# Math.net
KiCad netlist of a schematic drawn in EAGLE
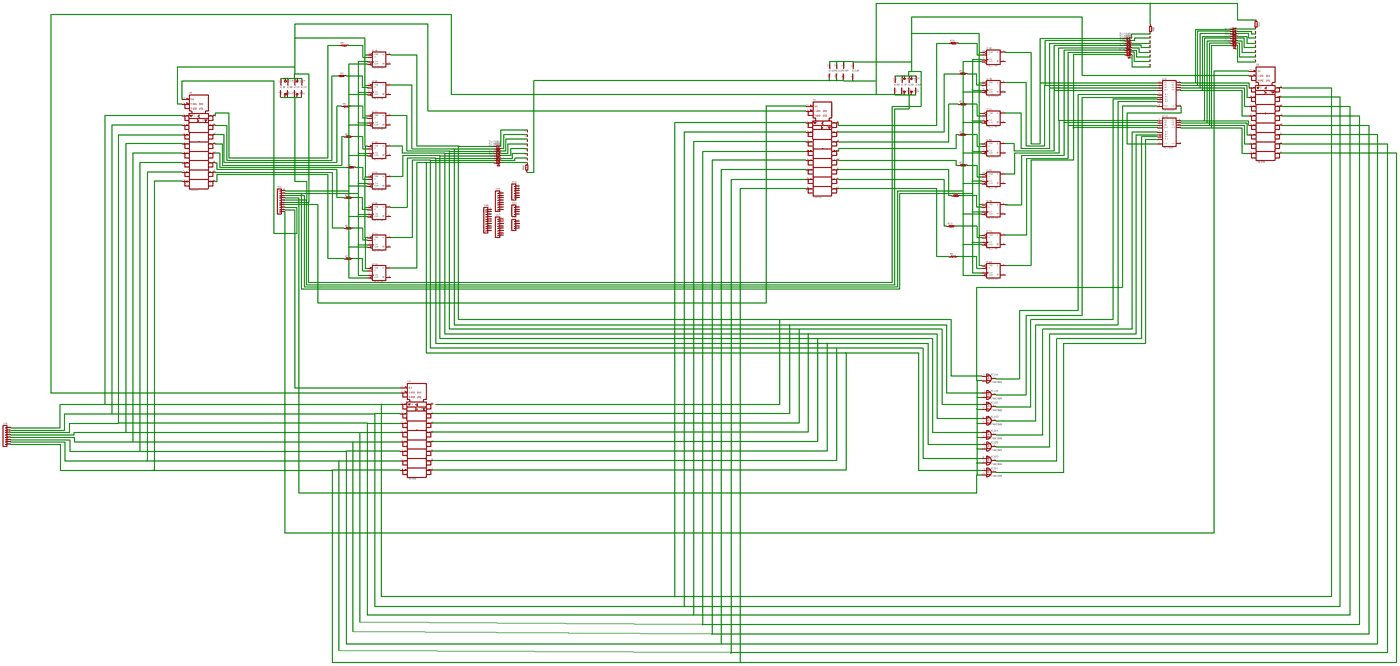
[diagram p0: schematic, sheet 1, overview]
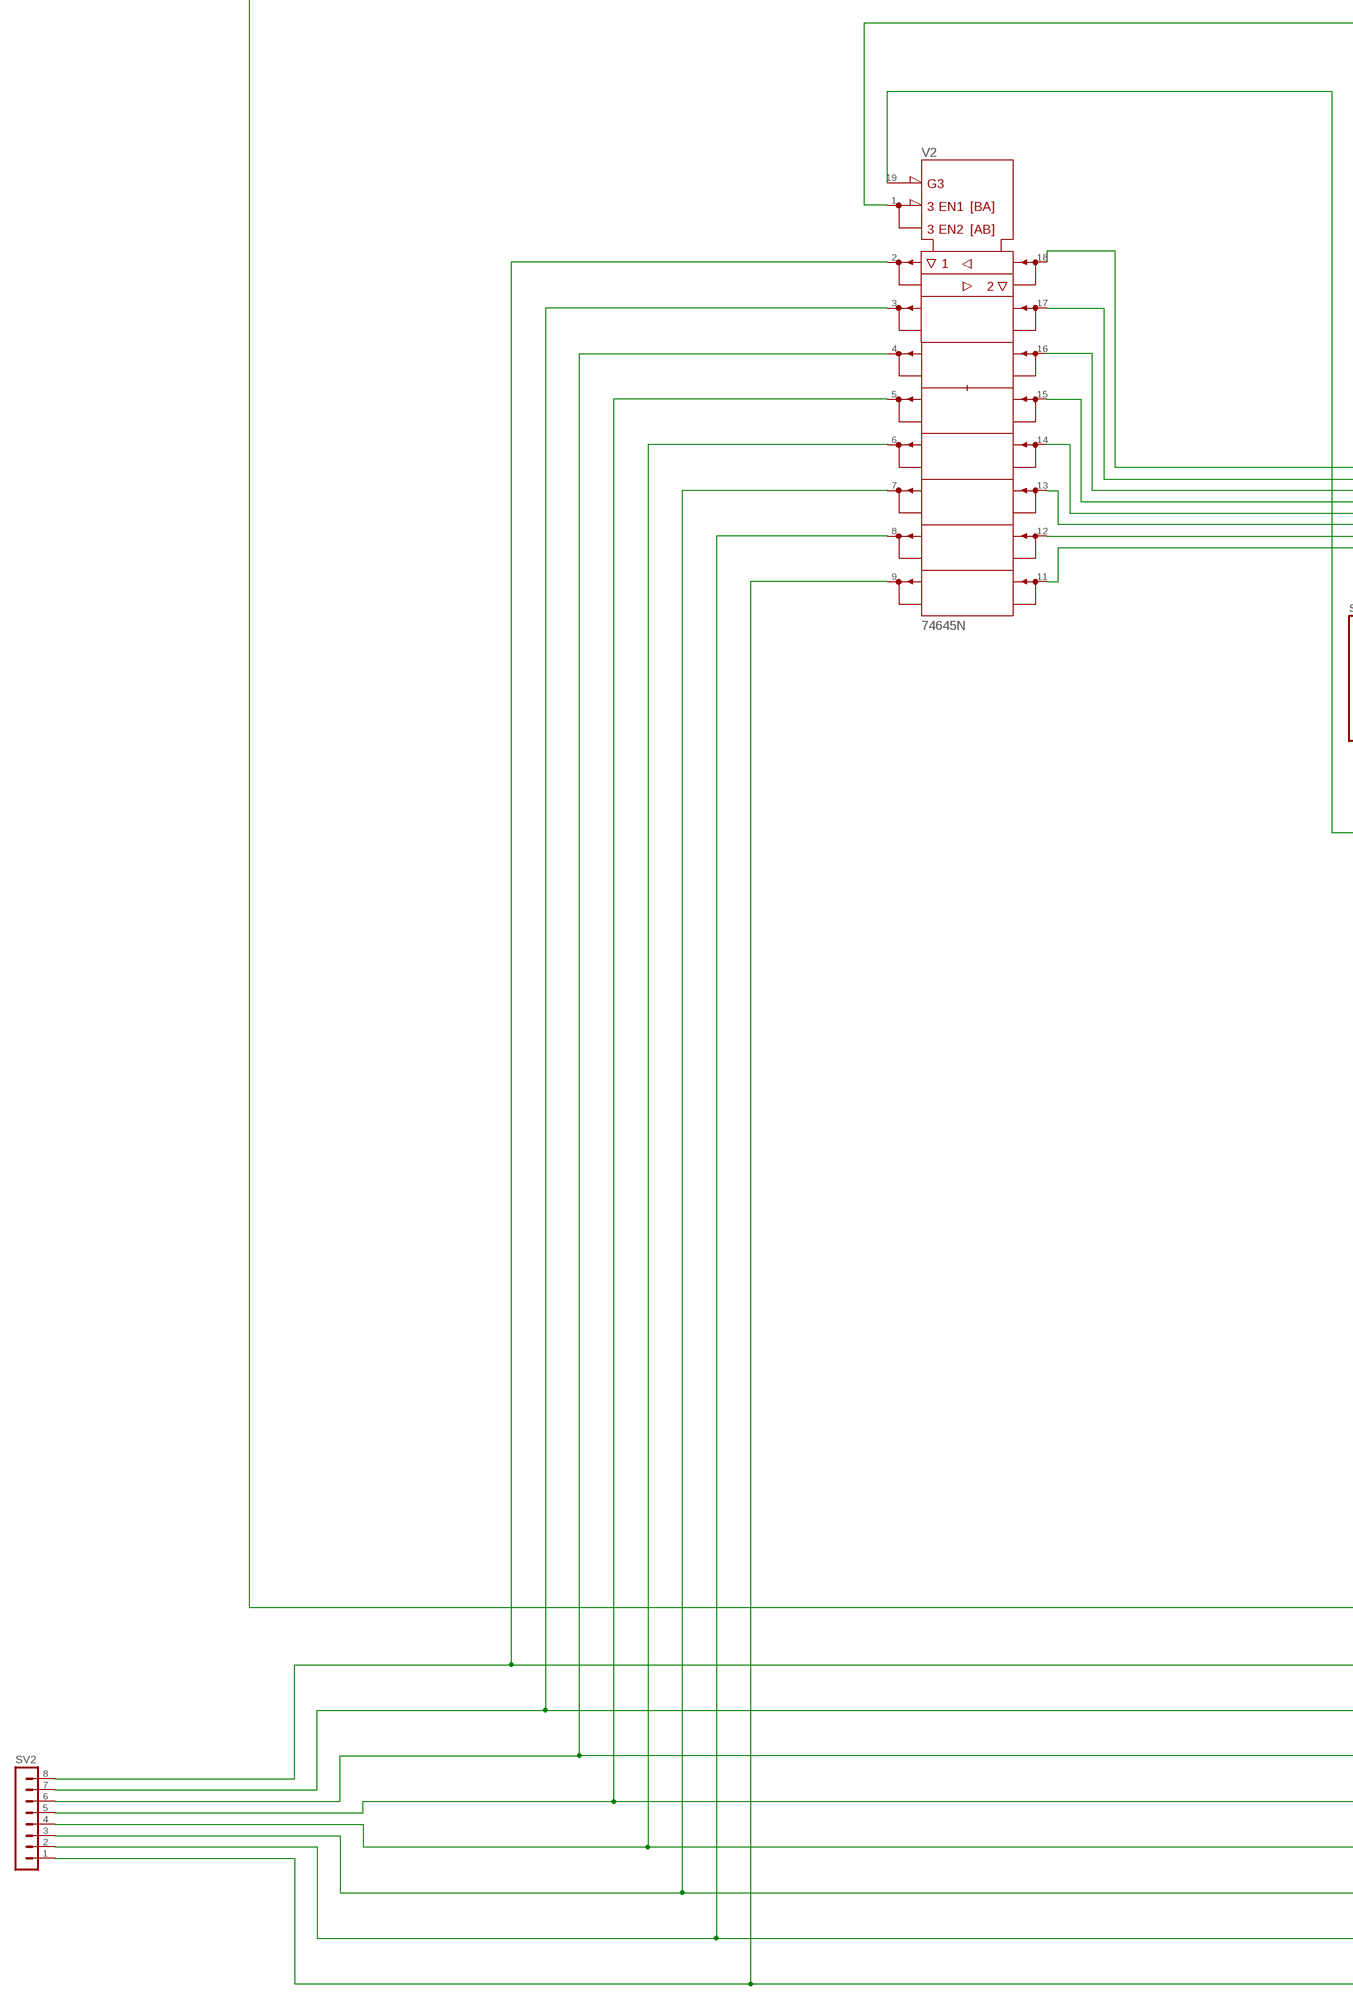
[diagram p1: schematic, sheet 1, part 1 of 6]
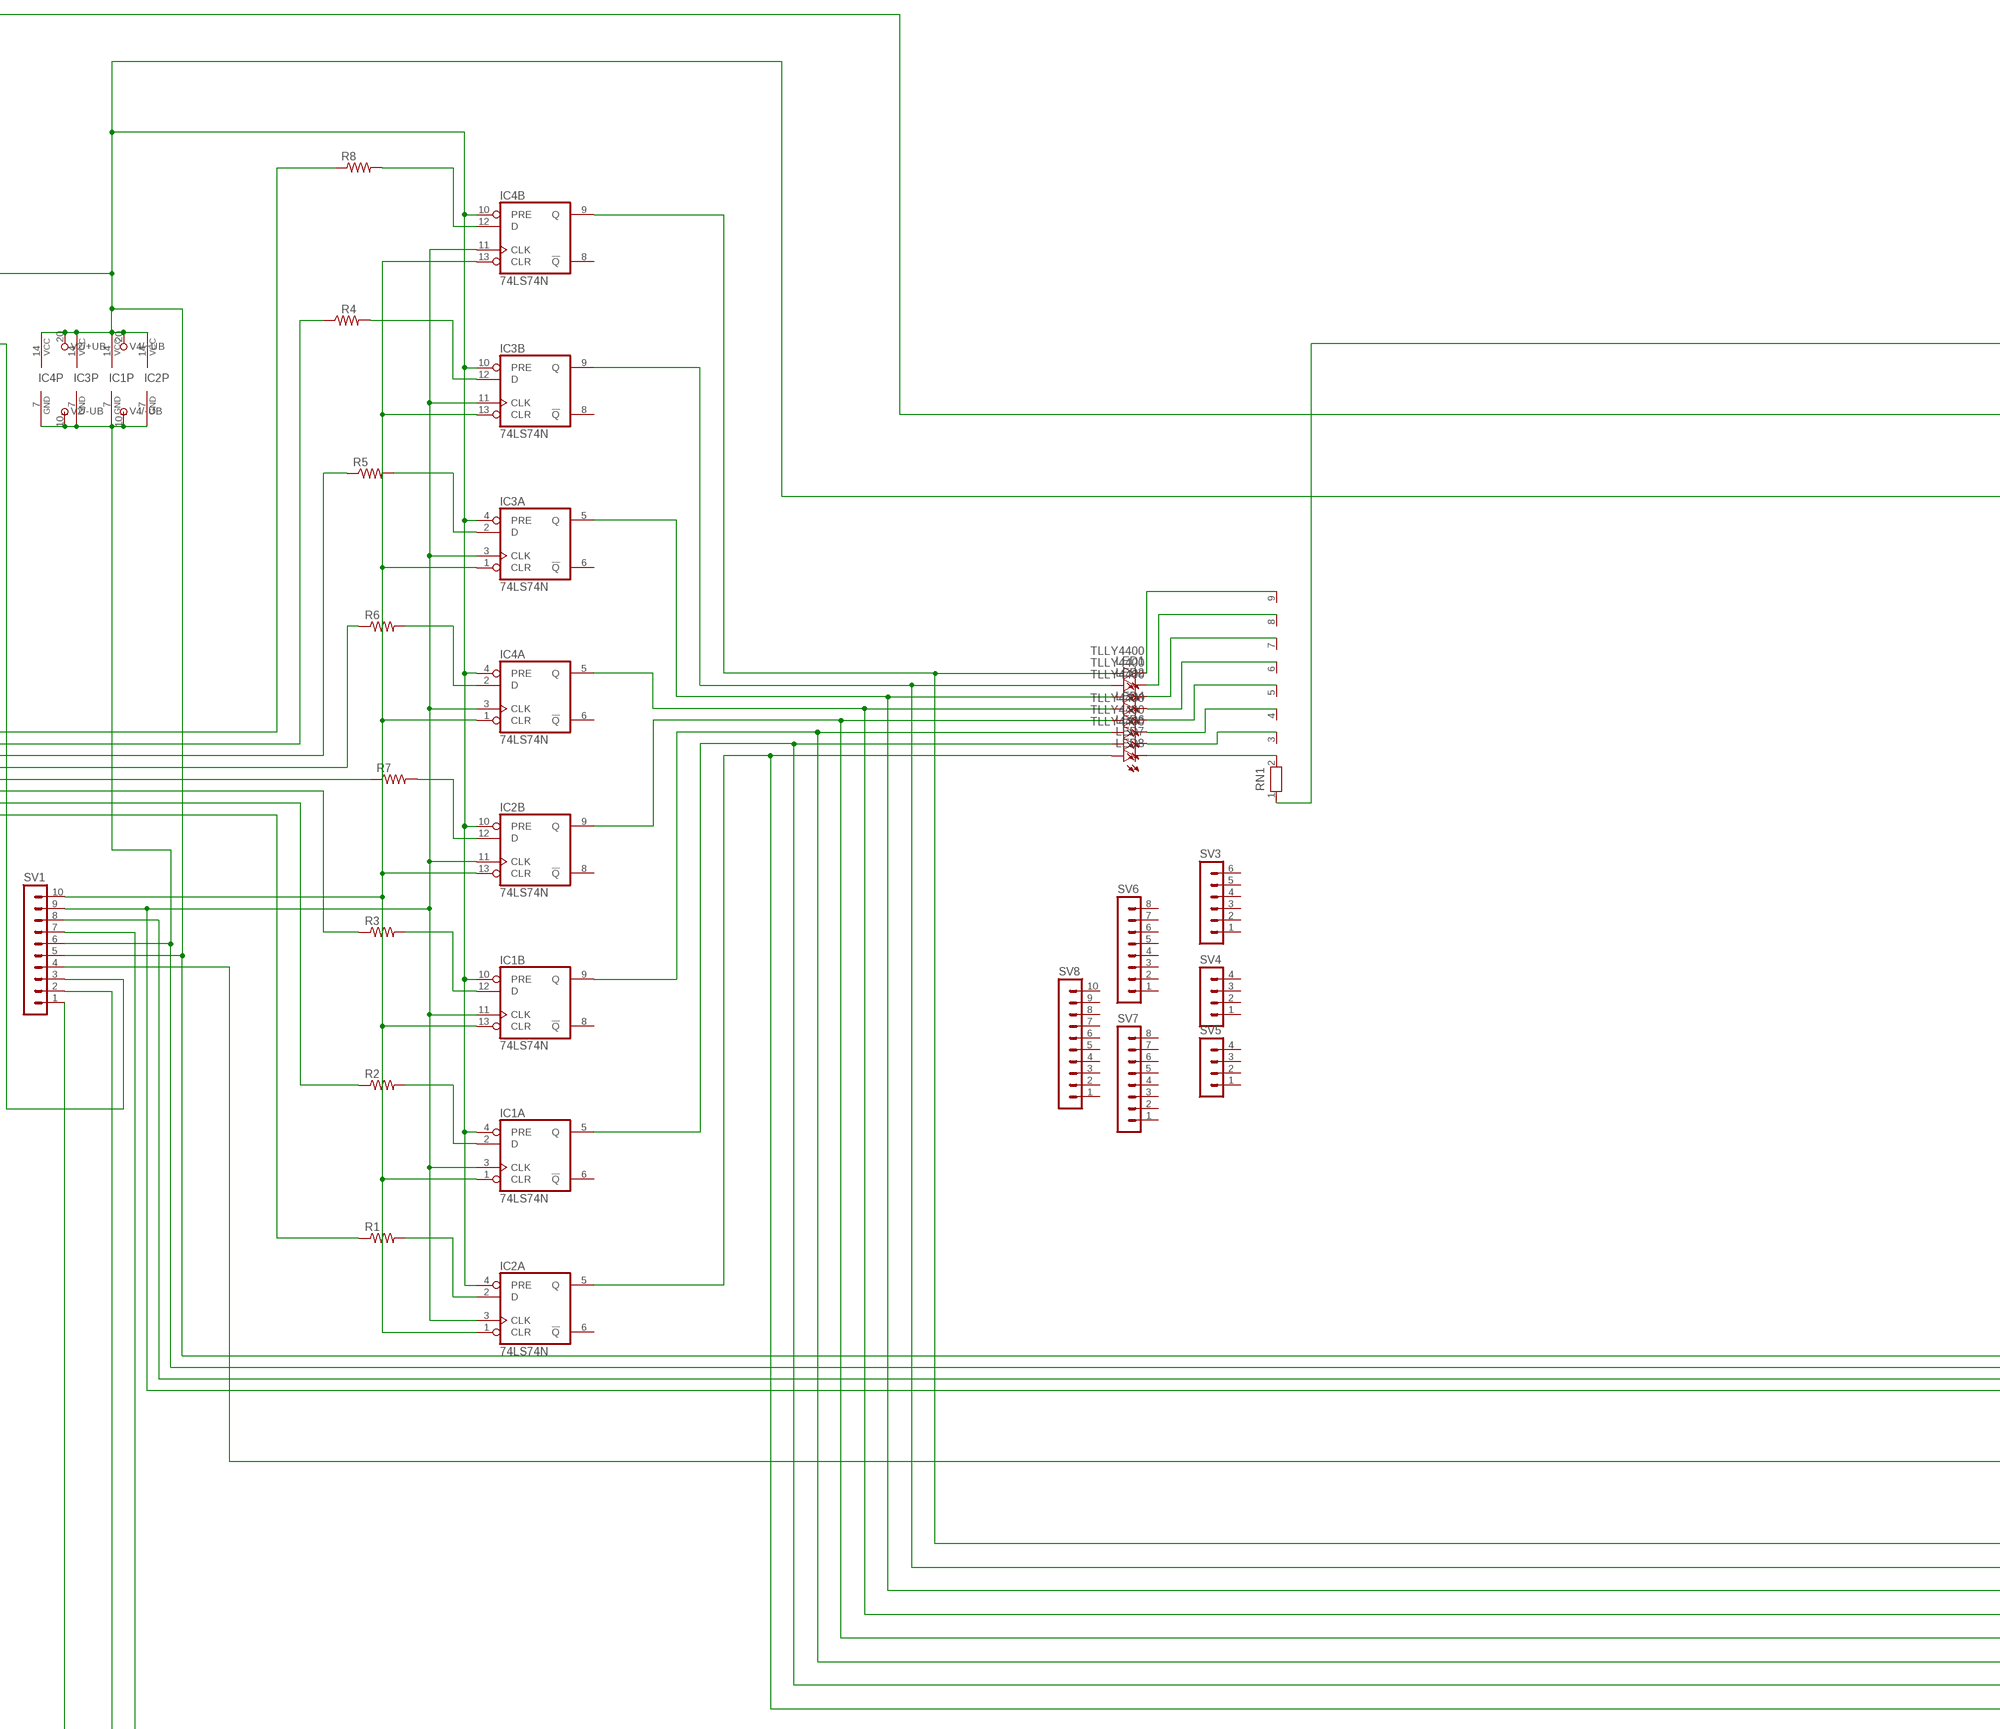
[diagram p2: schematic, sheet 1, part 2 of 6]
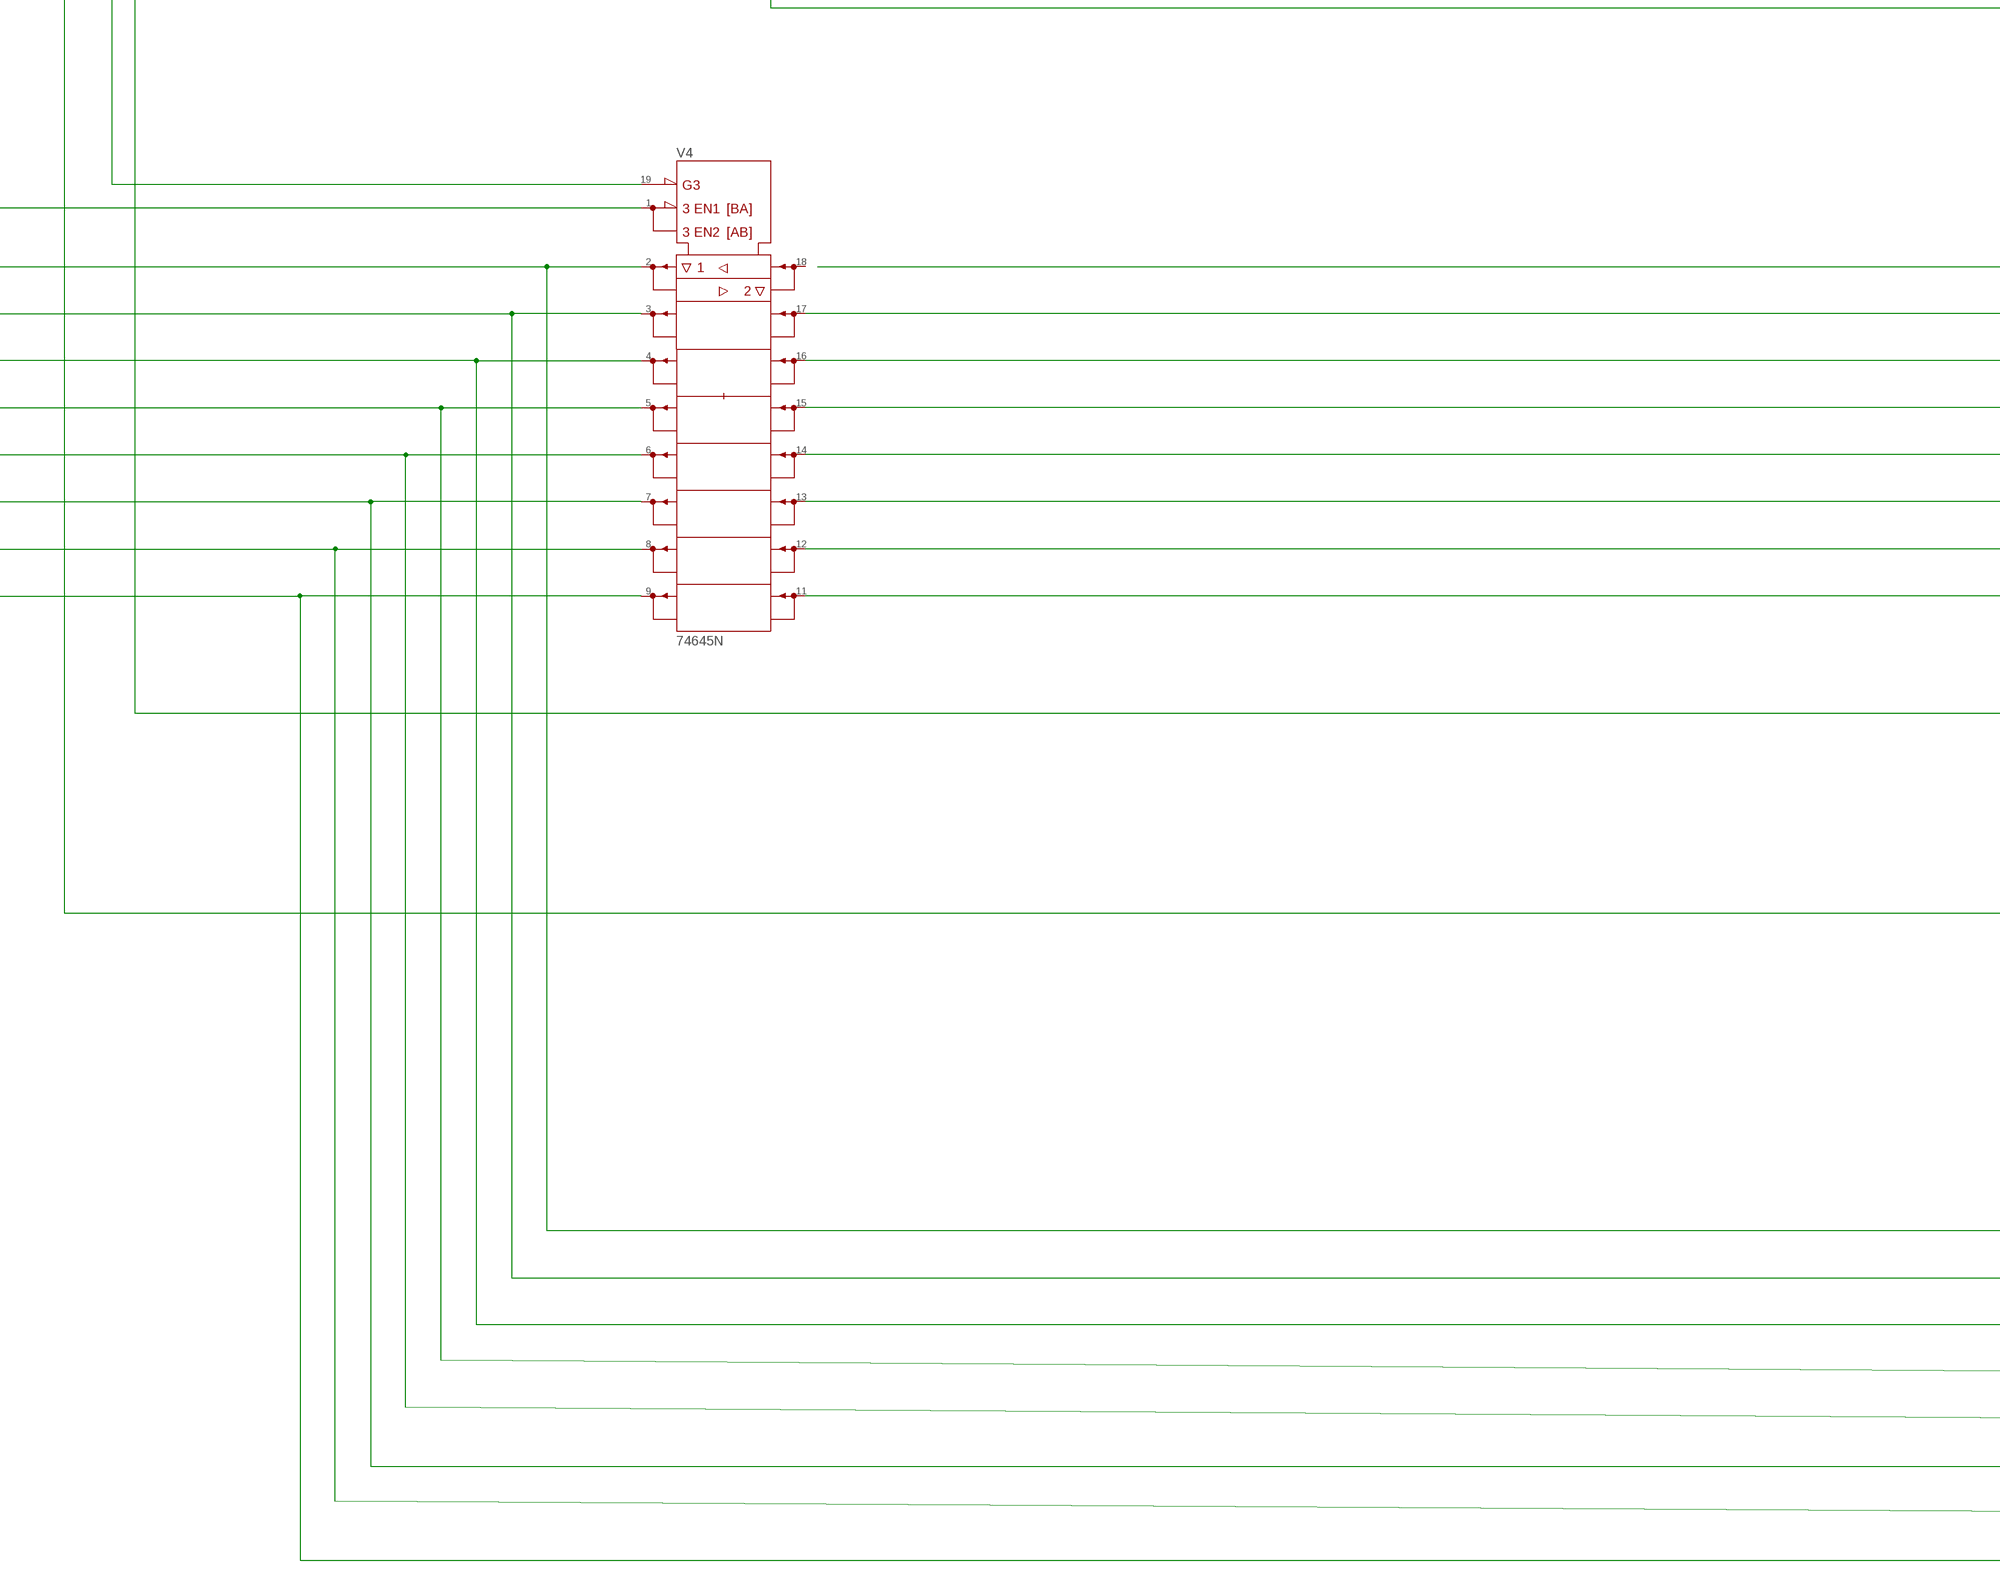
[diagram p3: schematic, sheet 1, part 3 of 6]
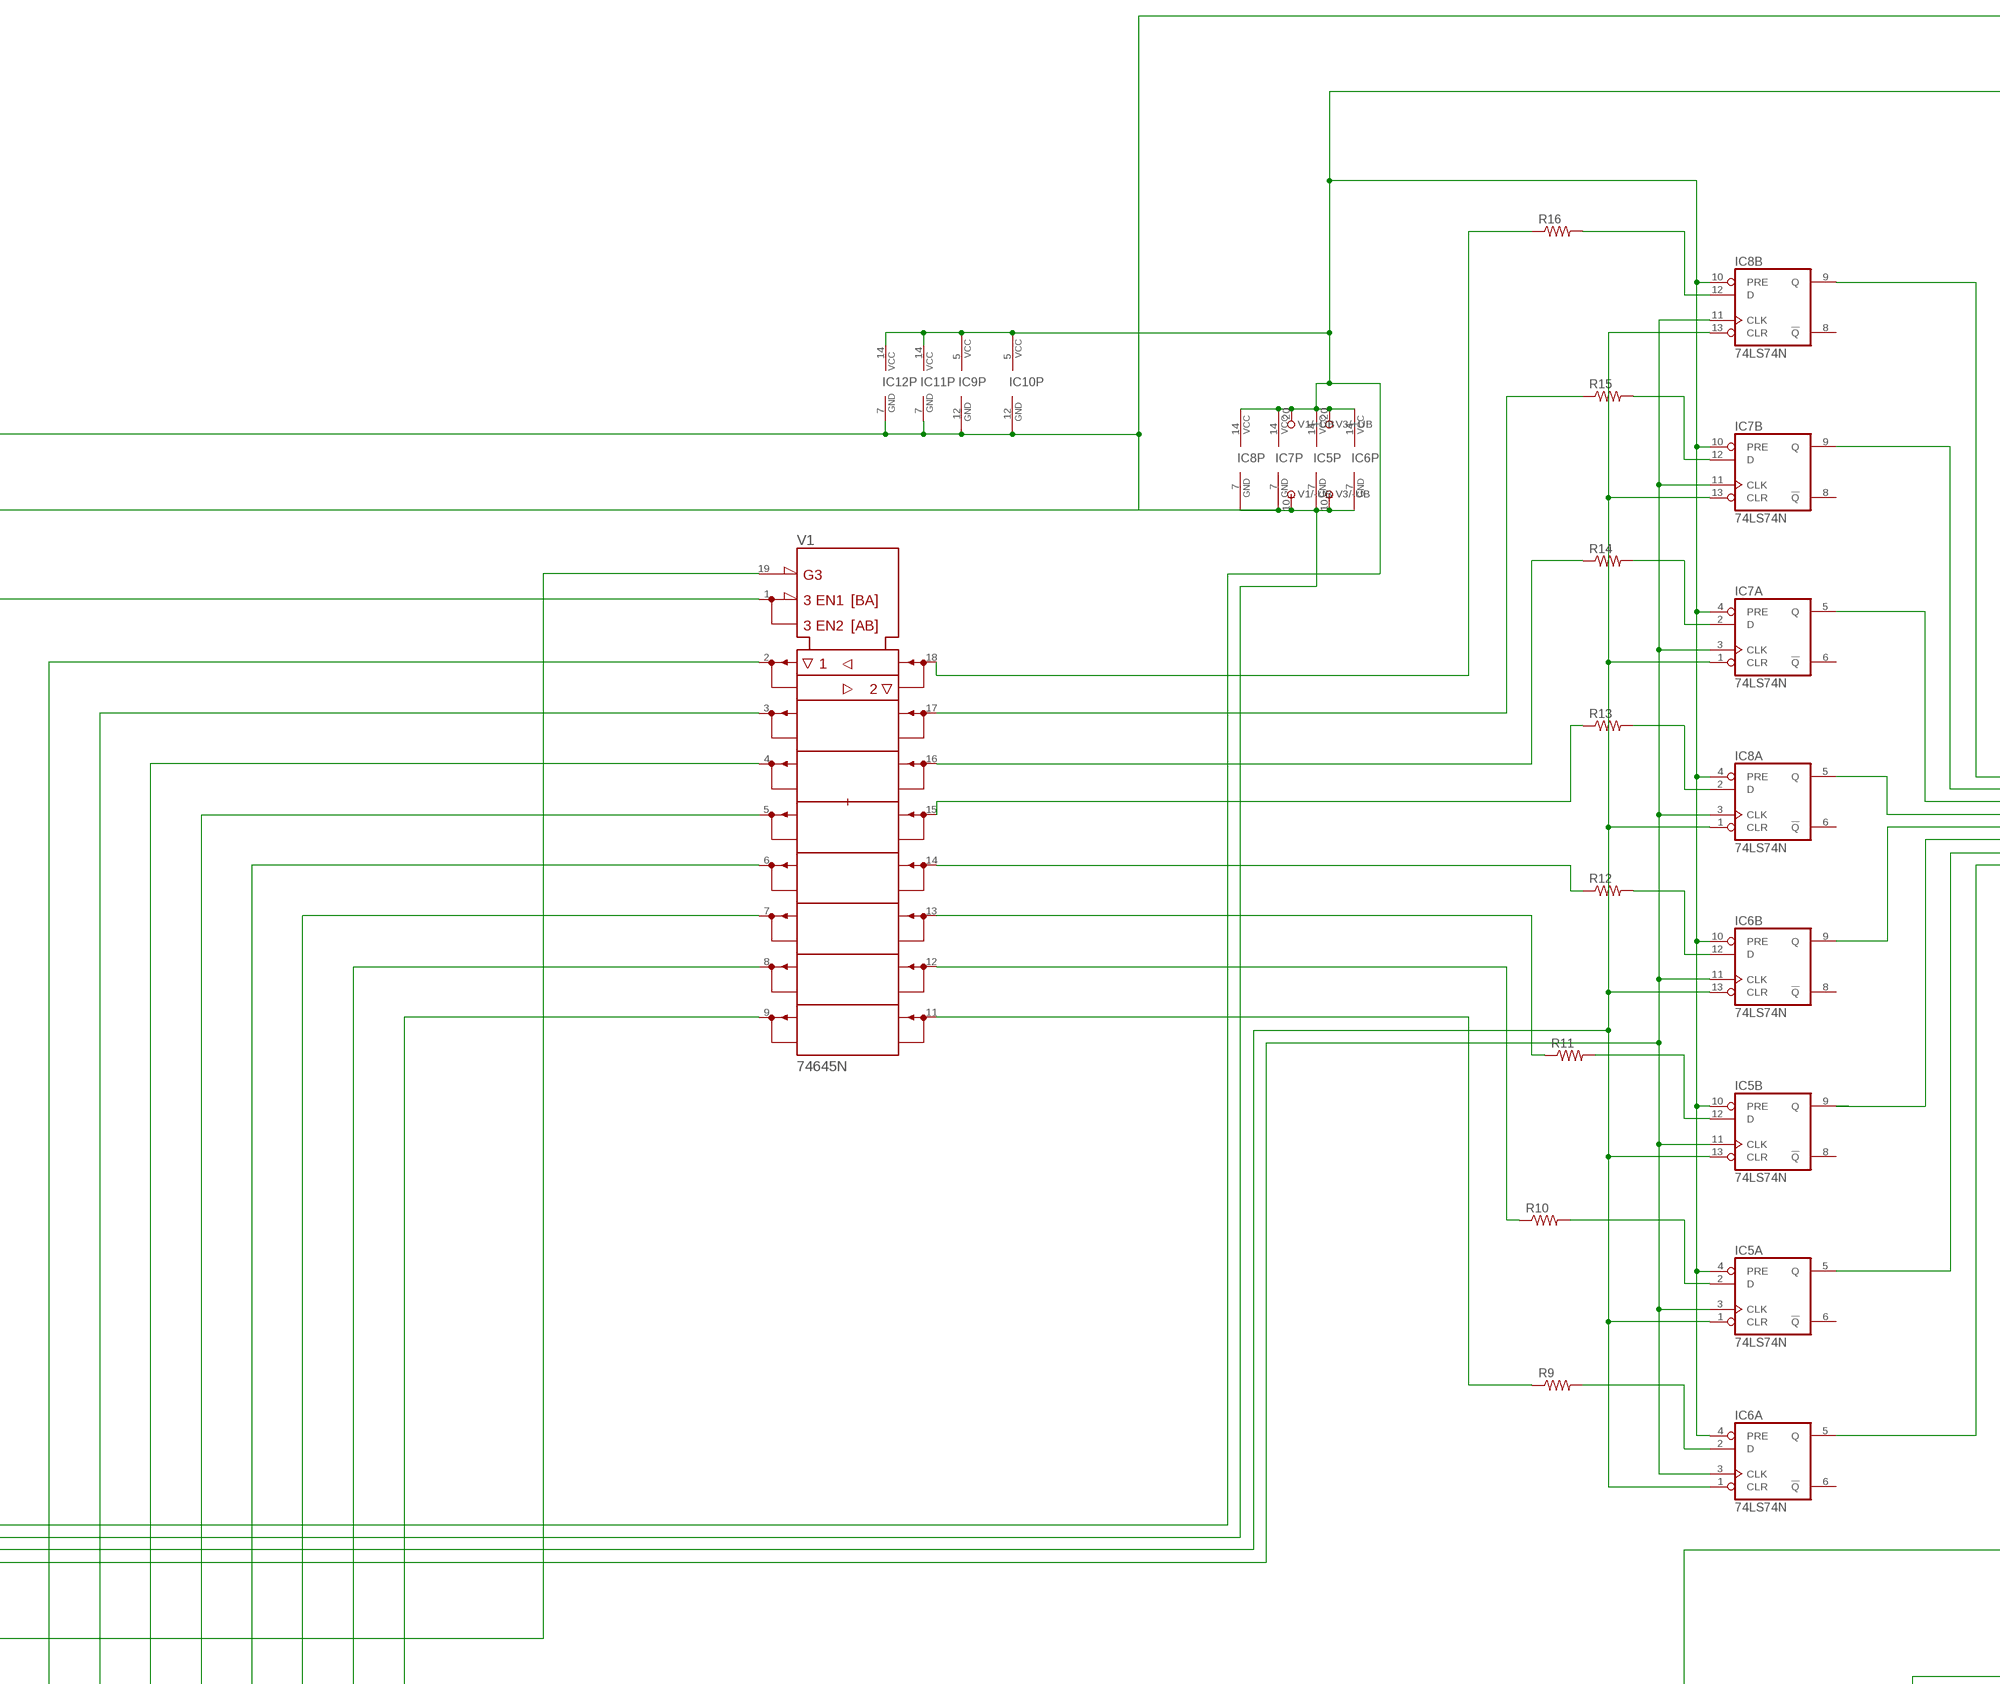
[diagram p4: schematic, sheet 1, part 4 of 6]
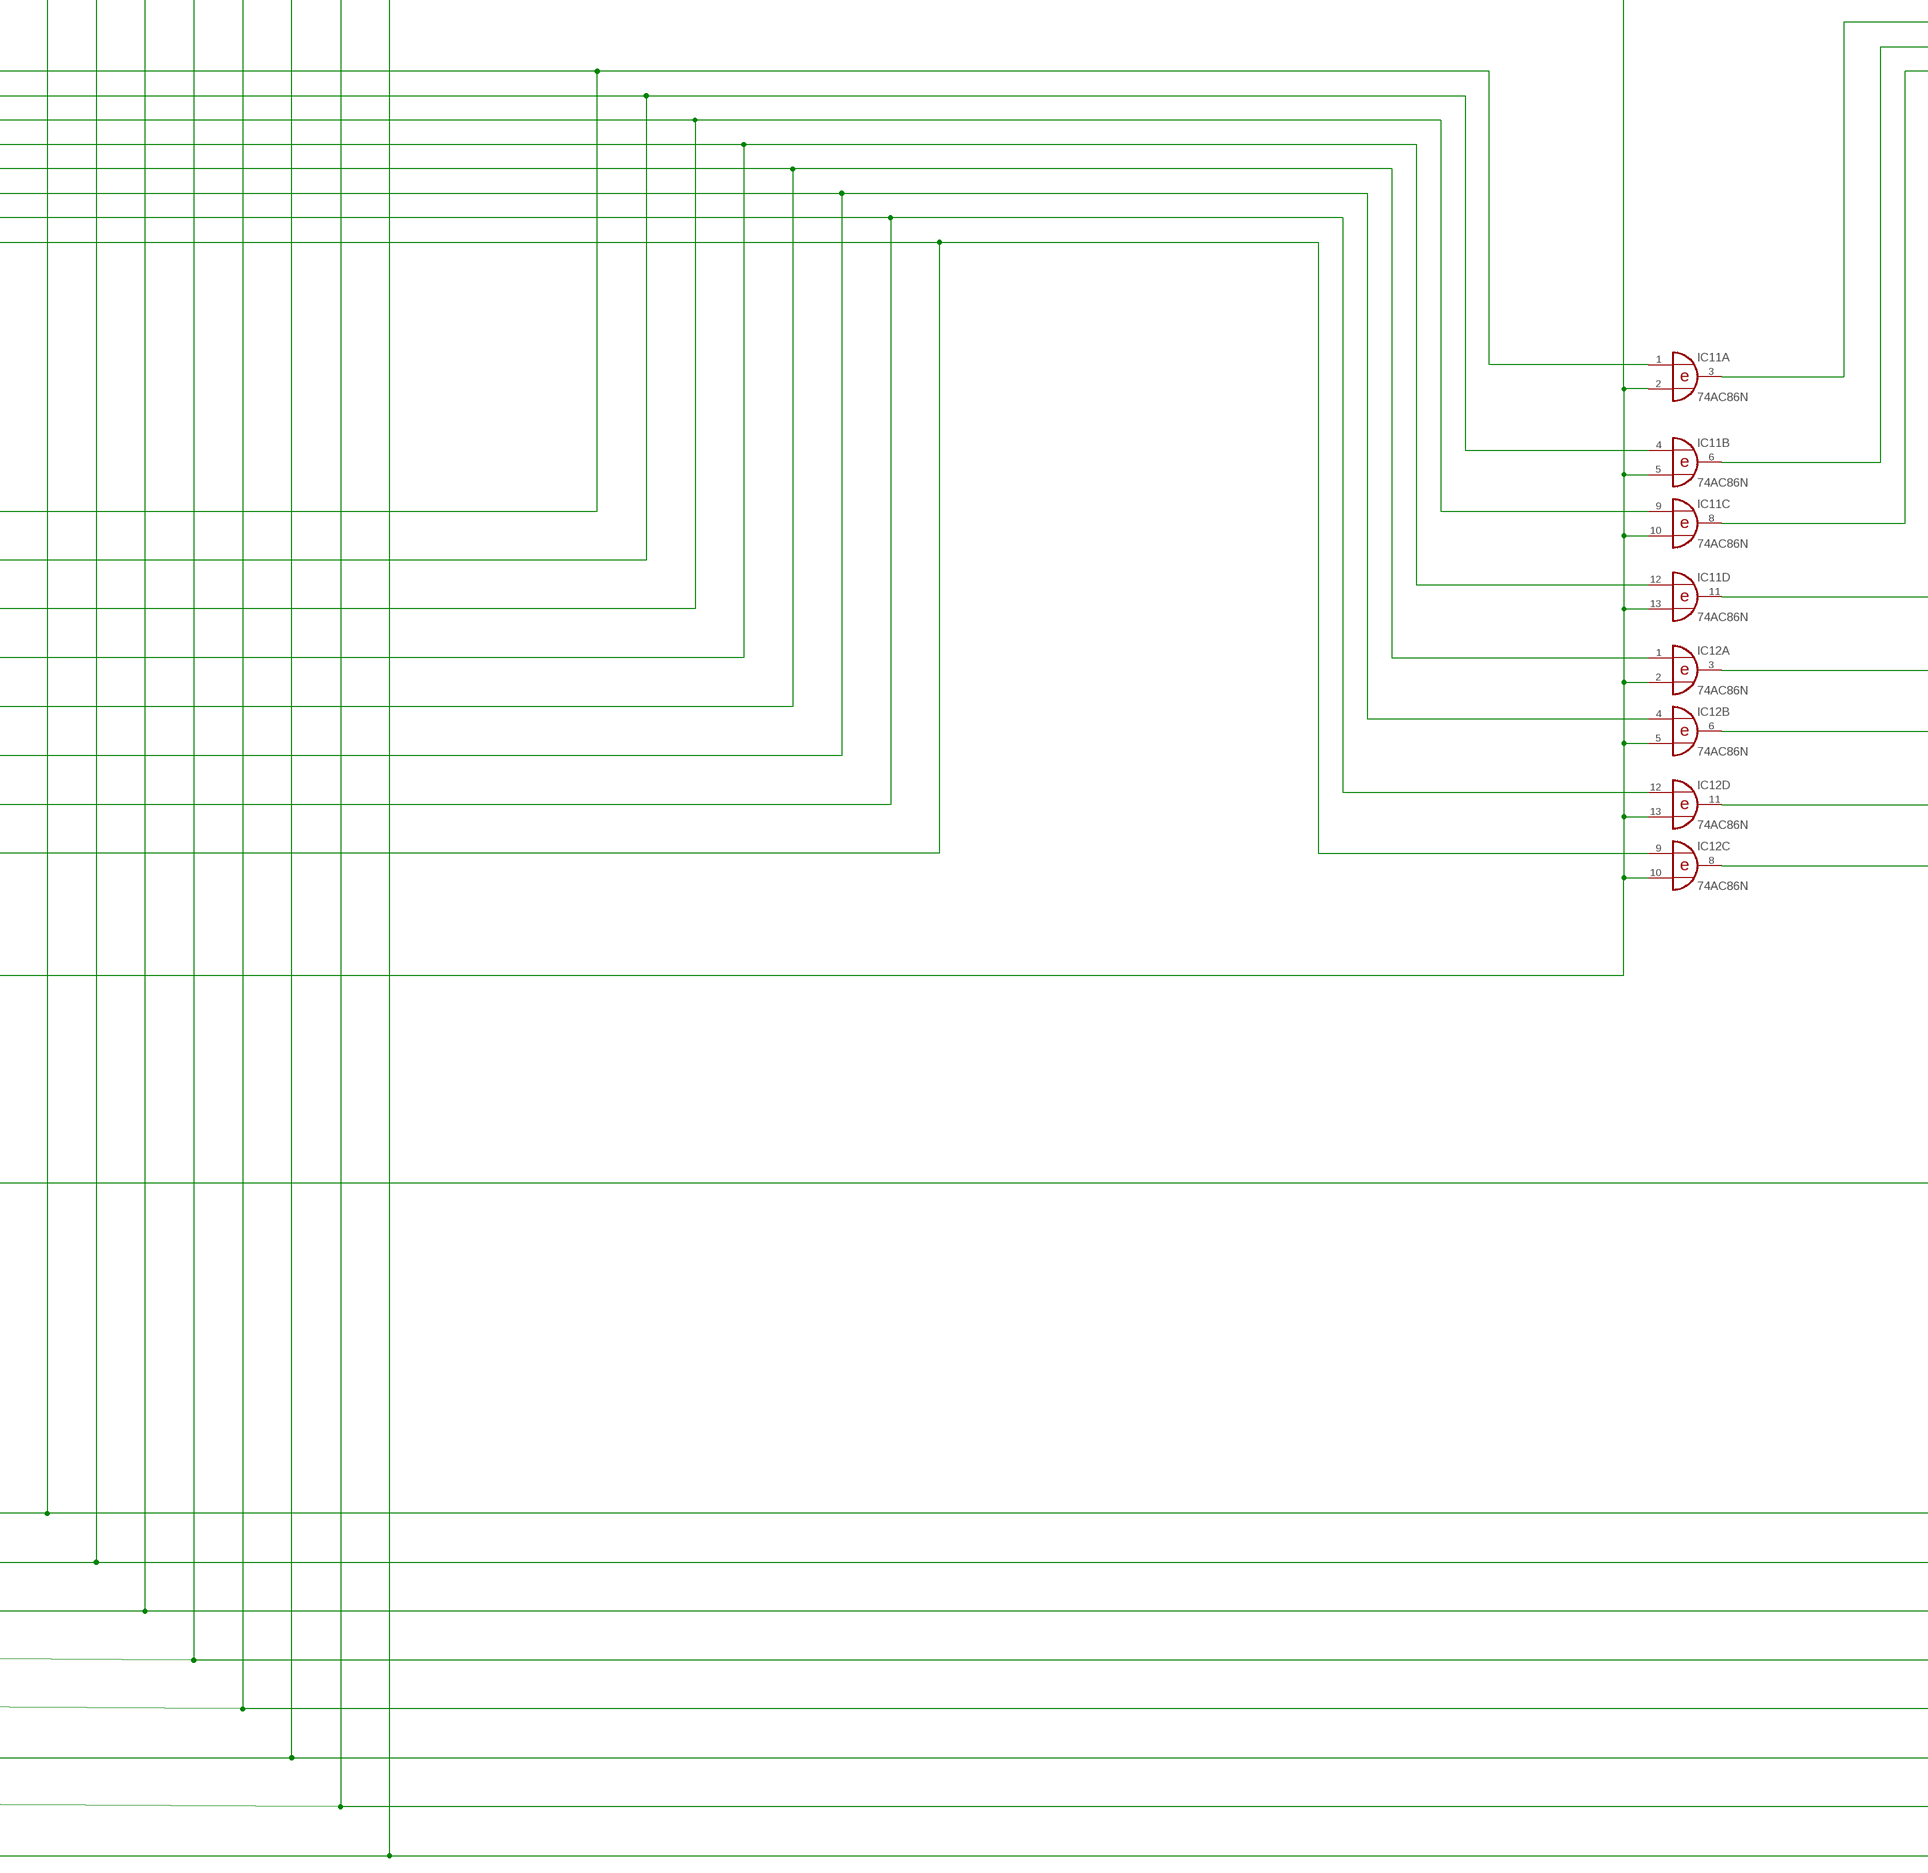
[diagram p5: schematic, sheet 1, part 5 of 6]
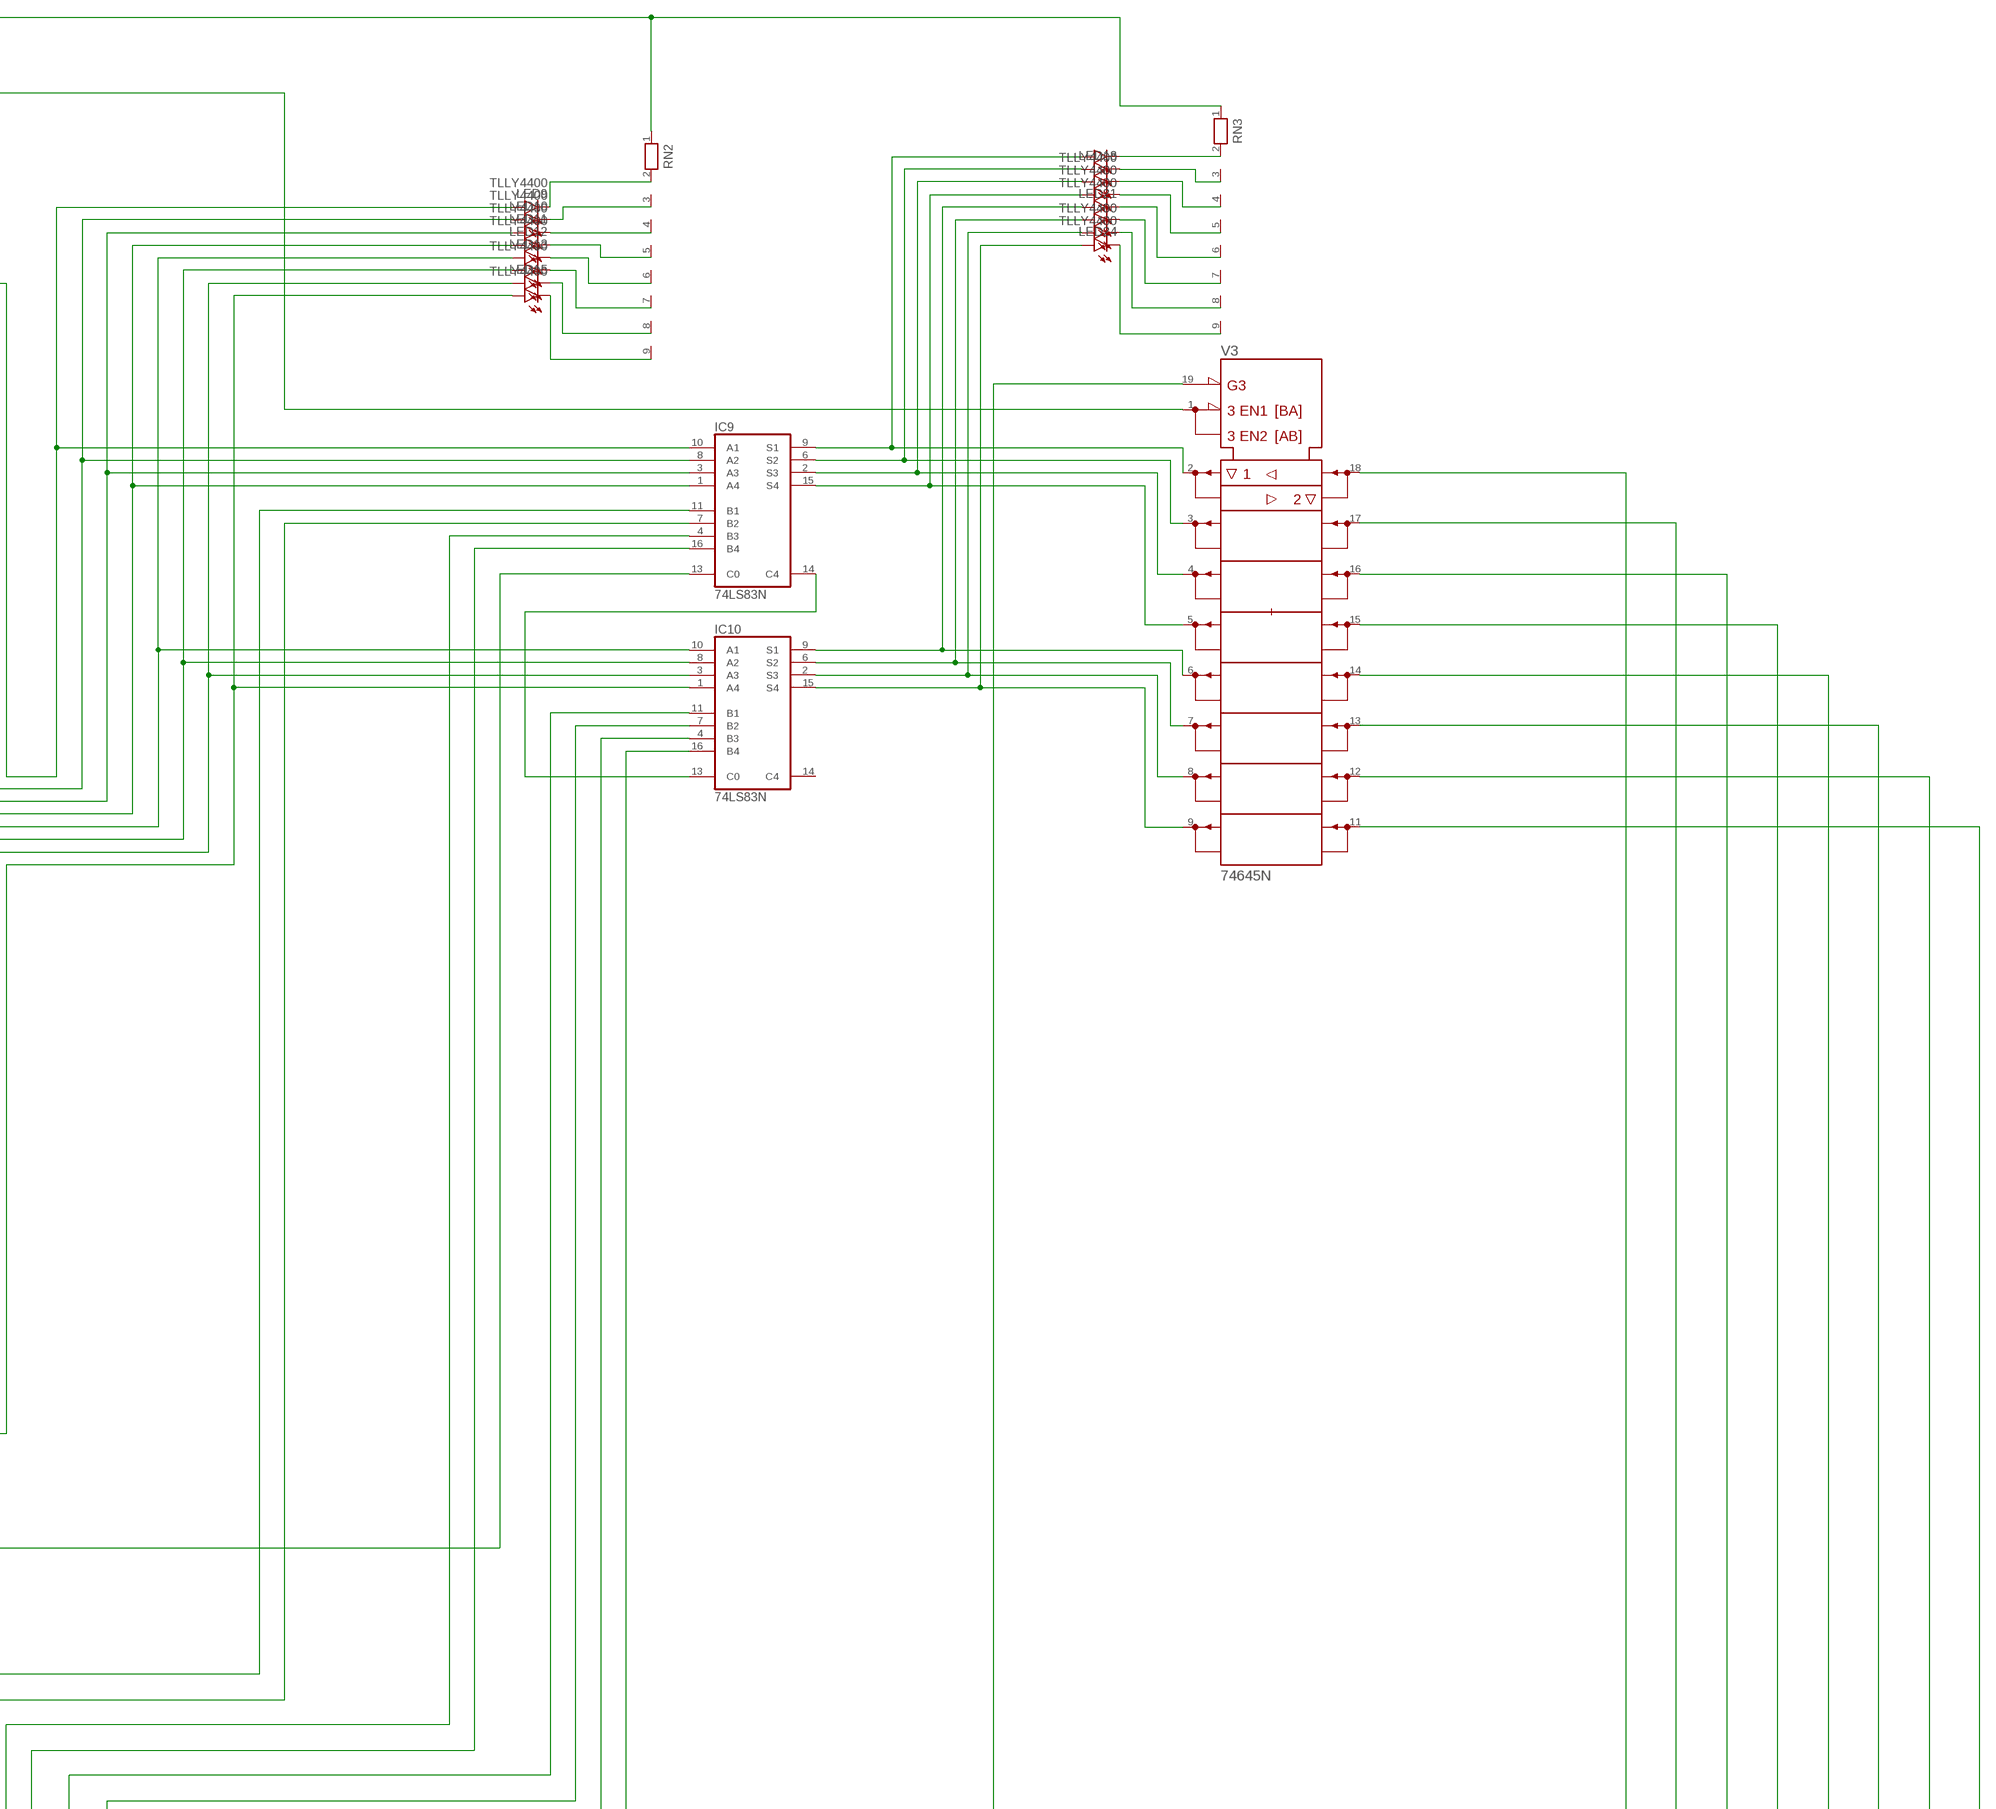
[diagram p6: schematic, sheet 1, part 6 of 6]

(export (version "E")
  (design (tool "Eeschema 10.0.6"))
  (components
    (comp (ref "IC1")
      (value "74LS74N")
      (footprint "eagle-import:DIL14")
      (libsource (lib "eagle-import") (part "7474NLS"))
    )
    (comp (ref "IC2")
      (value "74LS74N")
      (footprint "eagle-import:DIL14")
      (libsource (lib "eagle-import") (part "7474NLS"))
    )
    (comp (ref "IC3")
      (value "74LS74N")
      (footprint "eagle-import:DIL14")
      (libsource (lib "eagle-import") (part "7474NLS"))
    )
    (comp (ref "IC4")
      (value "74LS74N")
      (footprint "eagle-import:DIL14")
      (libsource (lib "eagle-import") (part "7474NLS"))
    )
    (comp (ref "IC5")
      (value "74LS74N")
      (footprint "eagle-import:DIL14")
      (libsource (lib "eagle-import") (part "7474NLS"))
    )
    (comp (ref "IC6")
      (value "74LS74N")
      (footprint "eagle-import:DIL14")
      (libsource (lib "eagle-import") (part "7474NLS"))
    )
    (comp (ref "IC7")
      (value "74LS74N")
      (footprint "eagle-import:DIL14")
      (libsource (lib "eagle-import") (part "7474NLS"))
    )
    (comp (ref "IC8")
      (value "74LS74N")
      (footprint "eagle-import:DIL14")
      (libsource (lib "eagle-import") (part "7474NLS"))
    )
    (comp (ref "IC9")
      (value "74LS83N")
      (footprint "eagle-import:DIL16")
      (libsource (lib "eagle-import") (part "7483NLS"))
    )
    (comp (ref "IC10")
      (value "74LS83N")
      (footprint "eagle-import:DIL16")
      (libsource (lib "eagle-import") (part "7483NLS"))
    )
    (comp (ref "IC11")
      (value "74AC86N")
      (footprint "eagle-import:DIL14")
      (libsource (lib "eagle-import") (part "7486NAC"))
    )
    (comp (ref "IC12")
      (value "74AC86N")
      (footprint "eagle-import:DIL14")
      (libsource (lib "eagle-import") (part "7486NAC"))
    )
    (comp (ref "LED1")
      (value "TLLY4400")
      (footprint "eagle-import:LED3MM")
      (fields (field (name "MF") "VISHAY SEMICONDUCTOR"))
      (libsource (lib "eagle-import") (part "TLLY4400"))
    )
    (comp (ref "LED2")
      (value "TLLY4400")
      (footprint "eagle-import:LED3MM")
      (fields (field (name "MF") "VISHAY SEMICONDUCTOR"))
      (libsource (lib "eagle-import") (part "TLLY4400"))
    )
    (comp (ref "LED3")
      (value "TLLY4400")
      (footprint "eagle-import:LED3MM")
      (fields (field (name "MF") "VISHAY SEMICONDUCTOR"))
      (libsource (lib "eagle-import") (part "TLLY4400"))
    )
    (comp (ref "LED4")
      (value "TLLY4400")
      (footprint "eagle-import:LED3MM")
      (fields (field (name "MF") "VISHAY SEMICONDUCTOR"))
      (libsource (lib "eagle-import") (part "TLLY4400"))
    )
    (comp (ref "LED5")
      (value "TLLY4400")
      (footprint "eagle-import:LED3MM")
      (fields (field (name "MF") "VISHAY SEMICONDUCTOR"))
      (libsource (lib "eagle-import") (part "TLLY4400"))
    )
    (comp (ref "LED6")
      (value "TLLY4400")
      (footprint "eagle-import:LED3MM")
      (fields (field (name "MF") "VISHAY SEMICONDUCTOR"))
      (libsource (lib "eagle-import") (part "TLLY4400"))
    )
    (comp (ref "LED7")
      (value "TLLY4400")
      (footprint "eagle-import:LED3MM")
      (fields (field (name "MF") "VISHAY SEMICONDUCTOR"))
      (libsource (lib "eagle-import") (part "TLLY4400"))
    )
    (comp (ref "LED8")
      (value "TLLY4400")
      (footprint "eagle-import:LED3MM")
      (fields (field (name "MF") "VISHAY SEMICONDUCTOR"))
      (libsource (lib "eagle-import") (part "TLLY4400"))
    )
    (comp (ref "LED9")
      (value "TLLY4400")
      (footprint "eagle-import:LED3MM")
      (fields (field (name "MF") "VISHAY SEMICONDUCTOR"))
      (libsource (lib "eagle-import") (part "TLLY4400"))
    )
    (comp (ref "LED10")
      (value "TLLY4400")
      (footprint "eagle-import:LED3MM")
      (fields (field (name "MF") "VISHAY SEMICONDUCTOR"))
      (libsource (lib "eagle-import") (part "TLLY4400"))
    )
    (comp (ref "LED11")
      (value "TLLY4400")
      (footprint "eagle-import:LED3MM")
      (fields (field (name "MF") "VISHAY SEMICONDUCTOR"))
      (libsource (lib "eagle-import") (part "TLLY4400"))
    )
    (comp (ref "LED12")
      (value "TLLY4400")
      (footprint "eagle-import:LED3MM")
      (fields (field (name "MF") "VISHAY SEMICONDUCTOR"))
      (libsource (lib "eagle-import") (part "TLLY4400"))
    )
    (comp (ref "LED13")
      (value "TLLY4400")
      (footprint "eagle-import:LED3MM")
      (fields (field (name "MF") "VISHAY SEMICONDUCTOR"))
      (libsource (lib "eagle-import") (part "TLLY4400"))
    )
    (comp (ref "LED14")
      (value "TLLY4400")
      (footprint "eagle-import:LED3MM")
      (fields (field (name "MF") "VISHAY SEMICONDUCTOR"))
      (libsource (lib "eagle-import") (part "TLLY4400"))
    )
    (comp (ref "LED15")
      (value "TLLY4400")
      (footprint "eagle-import:LED3MM")
      (fields (field (name "MF") "VISHAY SEMICONDUCTOR"))
      (libsource (lib "eagle-import") (part "TLLY4400"))
    )
    (comp (ref "LED16")
      (value "TLLY4400")
      (footprint "eagle-import:LED3MM")
      (fields (field (name "MF") "VISHAY SEMICONDUCTOR"))
      (libsource (lib "eagle-import") (part "TLLY4400"))
    )
    (comp (ref "LED17")
      (value "TLLY4400")
      (footprint "eagle-import:LED3MM")
      (fields (field (name "MF") "VISHAY SEMICONDUCTOR"))
      (libsource (lib "eagle-import") (part "TLLY4400"))
    )
    (comp (ref "LED18")
      (value "TLLY4400")
      (footprint "eagle-import:LED3MM")
      (fields (field (name "MF") "VISHAY SEMICONDUCTOR"))
      (libsource (lib "eagle-import") (part "TLLY4400"))
    )
    (comp (ref "LED19")
      (value "TLLY4400")
      (footprint "eagle-import:LED3MM")
      (fields (field (name "MF") "VISHAY SEMICONDUCTOR"))
      (libsource (lib "eagle-import") (part "TLLY4400"))
    )
    (comp (ref "LED20")
      (value "TLLY4400")
      (footprint "eagle-import:LED3MM")
      (fields (field (name "MF") "VISHAY SEMICONDUCTOR"))
      (libsource (lib "eagle-import") (part "TLLY4400"))
    )
    (comp (ref "LED21")
      (value "TLLY4400")
      (footprint "eagle-import:LED3MM")
      (fields (field (name "MF") "VISHAY SEMICONDUCTOR"))
      (libsource (lib "eagle-import") (part "TLLY4400"))
    )
    (comp (ref "LED22")
      (value "TLLY4400")
      (footprint "eagle-import:LED3MM")
      (fields (field (name "MF") "VISHAY SEMICONDUCTOR"))
      (libsource (lib "eagle-import") (part "TLLY4400"))
    )
    (comp (ref "LED23")
      (value "TLLY4400")
      (footprint "eagle-import:LED3MM")
      (fields (field (name "MF") "VISHAY SEMICONDUCTOR"))
      (libsource (lib "eagle-import") (part "TLLY4400"))
    )
    (comp (ref "LED24")
      (value "TLLY4400")
      (footprint "eagle-import:LED3MM")
      (fields (field (name "MF") "VISHAY SEMICONDUCTOR"))
      (libsource (lib "eagle-import") (part "TLLY4400"))
    )
    (comp (ref "R1")
      (value "R-US_0207/2V")
      (footprint "eagle-import:0207_2V")
      (libsource (lib "eagle-import") (part "R-US_0207/2V"))
    )
    (comp (ref "R2")
      (value "R-US_0207/2V")
      (footprint "eagle-import:0207_2V")
      (libsource (lib "eagle-import") (part "R-US_0207/2V"))
    )
    (comp (ref "R3")
      (value "R-US_0207/2V")
      (footprint "eagle-import:0207_2V")
      (libsource (lib "eagle-import") (part "R-US_0207/2V"))
    )
    (comp (ref "R4")
      (value "R-US_0207/2V")
      (footprint "eagle-import:0207_2V")
      (libsource (lib "eagle-import") (part "R-US_0207/2V"))
    )
    (comp (ref "R5")
      (value "R-US_0207/2V")
      (footprint "eagle-import:0207_2V")
      (libsource (lib "eagle-import") (part "R-US_0207/2V"))
    )
    (comp (ref "R6")
      (value "R-US_0207/2V")
      (footprint "eagle-import:0207_2V")
      (libsource (lib "eagle-import") (part "R-US_0207/2V"))
    )
    (comp (ref "R7")
      (value "R-US_0207/2V")
      (footprint "eagle-import:0207_2V")
      (libsource (lib "eagle-import") (part "R-US_0207/2V"))
    )
    (comp (ref "R8")
      (value "R-US_0207/2V")
      (footprint "eagle-import:0207_2V")
      (libsource (lib "eagle-import") (part "R-US_0207/2V"))
    )
    (comp (ref "R9")
      (value "R-US_0207/2V")
      (footprint "eagle-import:0207_2V")
      (libsource (lib "eagle-import") (part "R-US_0207/2V"))
    )
    (comp (ref "R10")
      (value "R-US_0207/2V")
      (footprint "eagle-import:0207_2V")
      (libsource (lib "eagle-import") (part "R-US_0207/2V"))
    )
    (comp (ref "R11")
      (value "R-US_0207/2V")
      (footprint "eagle-import:0207_2V")
      (libsource (lib "eagle-import") (part "R-US_0207/2V"))
    )
    (comp (ref "R12")
      (value "R-US_0207/2V")
      (footprint "eagle-import:0207_2V")
      (libsource (lib "eagle-import") (part "R-US_0207/2V"))
    )
    (comp (ref "R13")
      (value "R-US_0207/2V")
      (footprint "eagle-import:0207_2V")
      (libsource (lib "eagle-import") (part "R-US_0207/2V"))
    )
    (comp (ref "R14")
      (value "R-US_0207/2V")
      (footprint "eagle-import:0207_2V")
      (libsource (lib "eagle-import") (part "R-US_0207/2V"))
    )
    (comp (ref "R15")
      (value "R-US_0207/2V")
      (footprint "eagle-import:0207_2V")
      (libsource (lib "eagle-import") (part "R-US_0207/2V"))
    )
    (comp (ref "R16")
      (value "R-US_0207/2V")
      (footprint "eagle-import:0207_2V")
      (libsource (lib "eagle-import") (part "R-US_0207/2V"))
    )
    (comp (ref "RN1")
      (value "RN08")
      (footprint "eagle-import:RN-9")
      (libsource (lib "eagle-import") (part "RN08"))
    )
    (comp (ref "RN2")
      (value "RN08")
      (footprint "eagle-import:RN-9")
      (libsource (lib "eagle-import") (part "RN08"))
    )
    (comp (ref "RN3")
      (value "RN08")
      (footprint "eagle-import:RN-9")
      (libsource (lib "eagle-import") (part "RN08"))
    )
    (comp (ref "SV1")
      (value "MA10-1")
      (footprint "eagle-import:MA10-1")
      (libsource (lib "eagle-import") (part "MA10-1"))
    )
    (comp (ref "SV2")
      (value "MA08-1")
      (footprint "eagle-import:MA08-1")
      (libsource (lib "eagle-import") (part "MA08-1"))
    )
    (comp (ref "SV3")
      (value "MA06-1")
      (footprint "eagle-import:MA06-1")
      (libsource (lib "eagle-import") (part "MA06-1"))
    )
    (comp (ref "SV4")
      (value "MA04-1")
      (footprint "eagle-import:MA04-1")
      (libsource (lib "eagle-import") (part "MA04-1"))
    )
    (comp (ref "SV5")
      (value "MA04-1")
      (footprint "eagle-import:MA04-1")
      (libsource (lib "eagle-import") (part "MA04-1"))
    )
    (comp (ref "SV6")
      (value "MA08-1")
      (footprint "eagle-import:MA08-1")
      (libsource (lib "eagle-import") (part "MA08-1"))
    )
    (comp (ref "SV7")
      (value "MA08-1")
      (footprint "eagle-import:MA08-1")
      (libsource (lib "eagle-import") (part "MA08-1"))
    )
    (comp (ref "SV8")
      (value "MA10-1")
      (footprint "eagle-import:MA10-1")
      (libsource (lib "eagle-import") (part "MA10-1"))
    )
    (comp (ref "V1")
      (value "74645N")
      (footprint "eagle-import:DIL20")
      (libsource (lib "eagle-import") (part "74645N"))
    )
    (comp (ref "V2")
      (value "74645N")
      (footprint "eagle-import:DIL20")
      (libsource (lib "eagle-import") (part "74645N"))
    )
    (comp (ref "V3")
      (value "74645N")
      (footprint "eagle-import:DIL20")
      (libsource (lib "eagle-import") (part "74645N"))
    )
    (comp (ref "V4")
      (value "74645N")
      (footprint "eagle-import:DIL20")
      (libsource (lib "eagle-import") (part "74645N"))
    )
  )
  (nets
    (net (code "1") (name "Net-(IC1A-CLK)") (class "Default")
      (node (ref "IC1") (pin "11") (pinfunction "CLK_11") (pintype "input"))
      (node (ref "IC1") (pin "3") (pinfunction "CLK_3") (pintype "input"))
      (node (ref "IC2") (pin "11") (pinfunction "CLK_11") (pintype "input"))
      (node (ref "IC2") (pin "3") (pinfunction "CLK_3") (pintype "input"))
      (node (ref "IC3") (pin "11") (pinfunction "CLK_11") (pintype "input"))
      (node (ref "IC3") (pin "3") (pinfunction "CLK_3") (pintype "input"))
      (node (ref "IC4") (pin "11") (pinfunction "CLK_11") (pintype "input"))
      (node (ref "IC4") (pin "3") (pinfunction "CLK_3") (pintype "input"))
      (node (ref "IC5") (pin "11") (pinfunction "CLK_11") (pintype "input"))
      (node (ref "IC5") (pin "3") (pinfunction "CLK_3") (pintype "input"))
      (node (ref "IC6") (pin "11") (pinfunction "CLK_11") (pintype "input"))
      (node (ref "IC6") (pin "3") (pinfunction "CLK_3") (pintype "input"))
      (node (ref "IC7") (pin "11") (pinfunction "CLK_11") (pintype "input"))
      (node (ref "IC7") (pin "3") (pinfunction "CLK_3") (pintype "input"))
      (node (ref "IC8") (pin "11") (pinfunction "CLK_11") (pintype "input"))
      (node (ref "IC8") (pin "3") (pinfunction "CLK_3") (pintype "input"))
      (node (ref "SV1") (pin "9") (pinfunction "9_9") (pintype "passive"))
    )
    (net (code "2") (name "Net-(IC1A-CLR)") (class "Default")
      (node (ref "IC1") (pin "1") (pinfunction "CLR_1") (pintype "input"))
      (node (ref "IC1") (pin "13") (pinfunction "CLR_13") (pintype "input"))
      (node (ref "IC2") (pin "1") (pinfunction "CLR_1") (pintype "input"))
      (node (ref "IC2") (pin "13") (pinfunction "CLR_13") (pintype "input"))
      (node (ref "IC3") (pin "1") (pinfunction "CLR_1") (pintype "input"))
      (node (ref "IC3") (pin "13") (pinfunction "CLR_13") (pintype "input"))
      (node (ref "IC4") (pin "1") (pinfunction "CLR_1") (pintype "input"))
      (node (ref "IC4") (pin "13") (pinfunction "CLR_13") (pintype "input"))
      (node (ref "SV1") (pin "10") (pinfunction "10_10") (pintype "passive"))
    )
    (net (code "3") (name "Net-(IC1A-D)") (class "Default")
      (node (ref "IC1") (pin "2") (pinfunction "D_2") (pintype "input"))
      (node (ref "R2") (pin "2") (pinfunction "2_2") (pintype "passive"))
    )
    (net (code "4") (name "Net-(IC1B-D)") (class "Default")
      (node (ref "IC1") (pin "12") (pinfunction "D_12") (pintype "input"))
      (node (ref "R3") (pin "2") (pinfunction "2_2") (pintype "passive"))
    )
    (net (code "5") (name "Net-(IC2A-D)") (class "Default")
      (node (ref "IC2") (pin "2") (pinfunction "D_2") (pintype "input"))
      (node (ref "R1") (pin "2") (pinfunction "2_2") (pintype "passive"))
    )
    (net (code "6") (name "Net-(IC2B-D)") (class "Default")
      (node (ref "IC2") (pin "12") (pinfunction "D_12") (pintype "input"))
      (node (ref "R7") (pin "2") (pinfunction "2_2") (pintype "passive"))
    )
    (net (code "7") (name "Net-(IC3A-D)") (class "Default")
      (node (ref "IC3") (pin "2") (pinfunction "D_2") (pintype "input"))
      (node (ref "R5") (pin "2") (pinfunction "2_2") (pintype "passive"))
    )
    (net (code "8") (name "Net-(IC3B-D)") (class "Default")
      (node (ref "IC3") (pin "12") (pinfunction "D_12") (pintype "input"))
      (node (ref "R4") (pin "2") (pinfunction "2_2") (pintype "passive"))
    )
    (net (code "9") (name "Net-(IC4A-D)") (class "Default")
      (node (ref "IC4") (pin "2") (pinfunction "D_2") (pintype "input"))
      (node (ref "R6") (pin "2") (pinfunction "2_2") (pintype "passive"))
    )
    (net (code "10") (name "Net-(IC4B-D)") (class "Default")
      (node (ref "IC4") (pin "12") (pinfunction "D_12") (pintype "input"))
      (node (ref "R8") (pin "2") (pinfunction "2_2") (pintype "passive"))
    )
    (net (code "11") (name "Net-(IC5A-CLR)") (class "Default")
      (node (ref "IC5") (pin "1") (pinfunction "CLR_1") (pintype "input"))
      (node (ref "IC5") (pin "13") (pinfunction "CLR_13") (pintype "input"))
      (node (ref "IC6") (pin "1") (pinfunction "CLR_1") (pintype "input"))
      (node (ref "IC6") (pin "13") (pinfunction "CLR_13") (pintype "input"))
      (node (ref "IC7") (pin "1") (pinfunction "CLR_1") (pintype "input"))
      (node (ref "IC7") (pin "13") (pinfunction "CLR_13") (pintype "input"))
      (node (ref "IC8") (pin "1") (pinfunction "CLR_1") (pintype "input"))
      (node (ref "IC8") (pin "13") (pinfunction "CLR_13") (pintype "input"))
      (node (ref "SV1") (pin "8") (pinfunction "8_8") (pintype "passive"))
    )
    (net (code "12") (name "Net-(IC5A-D)") (class "Default")
      (node (ref "IC5") (pin "2") (pinfunction "D_2") (pintype "input"))
      (node (ref "R10") (pin "2") (pinfunction "2_2") (pintype "passive"))
    )
    (net (code "13") (name "Net-(IC5B-D)") (class "Default")
      (node (ref "IC5") (pin "12") (pinfunction "D_12") (pintype "input"))
      (node (ref "R11") (pin "2") (pinfunction "2_2") (pintype "passive"))
    )
    (net (code "14") (name "Net-(IC6A-D)") (class "Default")
      (node (ref "IC6") (pin "2") (pinfunction "D_2") (pintype "input"))
      (node (ref "R9") (pin "2") (pinfunction "2_2") (pintype "passive"))
    )
    (net (code "15") (name "Net-(IC6B-D)") (class "Default")
      (node (ref "IC6") (pin "12") (pinfunction "D_12") (pintype "input"))
      (node (ref "R12") (pin "2") (pinfunction "2_2") (pintype "passive"))
    )
    (net (code "16") (name "Net-(IC7A-D)") (class "Default")
      (node (ref "IC7") (pin "2") (pinfunction "D_2") (pintype "input"))
      (node (ref "R14") (pin "2") (pinfunction "2_2") (pintype "passive"))
    )
    (net (code "17") (name "Net-(IC7A-Q)") (class "Default")
      (node (ref "IC7") (pin "5") (pinfunction "Q_5") (pintype "output"))
      (node (ref "IC9") (pin "3") (pinfunction "A3_3") (pintype "input"))
      (node (ref "LED11") (pin "A") (pinfunction "A_A") (pintype "passive"))
    )
    (net (code "18") (name "Net-(IC7B-D)") (class "Default")
      (node (ref "IC7") (pin "12") (pinfunction "D_12") (pintype "input"))
      (node (ref "R15") (pin "2") (pinfunction "2_2") (pintype "passive"))
    )
    (net (code "19") (name "Net-(IC7B-Q)") (class "Default")
      (node (ref "IC7") (pin "9") (pinfunction "Q_9") (pintype "output"))
      (node (ref "IC9") (pin "8") (pinfunction "A2_8") (pintype "input"))
      (node (ref "LED10") (pin "A") (pinfunction "A_A") (pintype "passive"))
    )
    (net (code "20") (name "Net-(IC8A-D)") (class "Default")
      (node (ref "IC8") (pin "2") (pinfunction "D_2") (pintype "input"))
      (node (ref "R13") (pin "2") (pinfunction "2_2") (pintype "passive"))
    )
    (net (code "21") (name "Net-(IC8A-Q)") (class "Default")
      (node (ref "IC8") (pin "5") (pinfunction "Q_5") (pintype "output"))
      (node (ref "IC9") (pin "1") (pinfunction "A4_1") (pintype "input"))
      (node (ref "LED12") (pin "A") (pinfunction "A_A") (pintype "passive"))
    )
    (net (code "22") (name "Net-(IC8B-D)") (class "Default")
      (node (ref "IC8") (pin "12") (pinfunction "D_12") (pintype "input"))
      (node (ref "R16") (pin "2") (pinfunction "2_2") (pintype "passive"))
    )
    (net (code "23") (name "Net-(IC8B-Q)") (class "Default")
      (node (ref "IC8") (pin "9") (pinfunction "Q_9") (pintype "output"))
      (node (ref "IC9") (pin "10") (pinfunction "A1_10") (pintype "input"))
      (node (ref "LED9") (pin "A") (pinfunction "A_A") (pintype "passive"))
    )
    (net (code "24") (name "Net-(IC9A-S1)") (class "Default")
      (node (ref "IC9") (pin "9") (pinfunction "S1_9") (pintype "output"))
      (node (ref "LED17") (pin "A") (pinfunction "A_A") (pintype "passive"))
      (node (ref "V3") (pin "2") (pinfunction "A1_2") (pintype "bidirectional"))
    )
    (net (code "25") (name "Net-(IC9A-S2)") (class "Default")
      (node (ref "IC9") (pin "6") (pinfunction "S2_6") (pintype "output"))
      (node (ref "LED18") (pin "A") (pinfunction "A_A") (pintype "passive"))
      (node (ref "V3") (pin "3") (pinfunction "A2_3") (pintype "bidirectional"))
    )
    (net (code "26") (name "Net-(IC9A-S3)") (class "Default")
      (node (ref "IC9") (pin "2") (pinfunction "S3_2") (pintype "output"))
      (node (ref "LED19") (pin "A") (pinfunction "A_A") (pintype "passive"))
      (node (ref "V3") (pin "4") (pinfunction "A3_4") (pintype "bidirectional"))
    )
    (net (code "27") (name "Net-(IC9A-S4)") (class "Default")
      (node (ref "IC9") (pin "15") (pinfunction "S4_15") (pintype "output"))
      (node (ref "LED20") (pin "A") (pinfunction "A_A") (pintype "passive"))
      (node (ref "V3") (pin "5") (pinfunction "A4_5") (pintype "bidirectional"))
    )
    (net (code "28") (name "Net-(IC10A-A1)") (class "Default")
      (node (ref "IC10") (pin "10") (pinfunction "A1_10") (pintype "input"))
      (node (ref "IC6") (pin "9") (pinfunction "Q_9") (pintype "output"))
      (node (ref "LED13") (pin "A") (pinfunction "A_A") (pintype "passive"))
    )
    (net (code "29") (name "Net-(IC10A-A2)") (class "Default")
      (node (ref "IC10") (pin "8") (pinfunction "A2_8") (pintype "input"))
      (node (ref "IC5") (pin "9") (pinfunction "Q_9") (pintype "output"))
      (node (ref "LED14") (pin "A") (pinfunction "A_A") (pintype "passive"))
    )
    (net (code "30") (name "Net-(IC10A-A3)") (class "Default")
      (node (ref "IC10") (pin "3") (pinfunction "A3_3") (pintype "input"))
      (node (ref "IC5") (pin "5") (pinfunction "Q_5") (pintype "output"))
      (node (ref "LED15") (pin "A") (pinfunction "A_A") (pintype "passive"))
    )
    (net (code "31") (name "Net-(IC10A-A4)") (class "Default")
      (node (ref "IC10") (pin "1") (pinfunction "A4_1") (pintype "input"))
      (node (ref "IC6") (pin "5") (pinfunction "Q_5") (pintype "output"))
      (node (ref "LED16") (pin "A") (pinfunction "A_A") (pintype "passive"))
    )
    (net (code "32") (name "Net-(IC10A-B1)") (class "Default")
      (node (ref "IC10") (pin "11") (pinfunction "B1_11") (pintype "input"))
      (node (ref "IC12") (pin "3") (pinfunction "O_3") (pintype "output"))
    )
    (net (code "33") (name "Net-(IC10A-B2)") (class "Default")
      (node (ref "IC10") (pin "7") (pinfunction "B2_7") (pintype "input"))
      (node (ref "IC12") (pin "6") (pinfunction "O_6") (pintype "output"))
    )
    (net (code "34") (name "Net-(IC10A-B3)") (class "Default")
      (node (ref "IC10") (pin "4") (pinfunction "B3_4") (pintype "input"))
      (node (ref "IC12") (pin "11") (pinfunction "O_11") (pintype "output"))
    )
    (net (code "35") (name "Net-(IC10A-B4)") (class "Default")
      (node (ref "IC10") (pin "16") (pinfunction "B4_16") (pintype "input"))
      (node (ref "IC12") (pin "8") (pinfunction "O_8") (pintype "output"))
    )
    (net (code "36") (name "Net-(IC10A-C0)") (class "Default")
      (node (ref "IC10") (pin "13") (pinfunction "C0_13") (pintype "input"))
      (node (ref "IC9") (pin "14") (pinfunction "C4_14") (pintype "output"))
    )
    (net (code "37") (name "Net-(IC10A-S1)") (class "Default")
      (node (ref "IC10") (pin "9") (pinfunction "S1_9") (pintype "output"))
      (node (ref "LED21") (pin "A") (pinfunction "A_A") (pintype "passive"))
      (node (ref "V3") (pin "6") (pinfunction "A5_6") (pintype "bidirectional"))
    )
    (net (code "38") (name "Net-(IC10A-S2)") (class "Default")
      (node (ref "IC10") (pin "6") (pinfunction "S2_6") (pintype "output"))
      (node (ref "LED22") (pin "A") (pinfunction "A_A") (pintype "passive"))
      (node (ref "V3") (pin "7") (pinfunction "A6_7") (pintype "bidirectional"))
    )
    (net (code "39") (name "Net-(IC10A-S3)") (class "Default")
      (node (ref "IC10") (pin "2") (pinfunction "S3_2") (pintype "output"))
      (node (ref "LED23") (pin "A") (pinfunction "A_A") (pintype "passive"))
      (node (ref "V3") (pin "8") (pinfunction "A7_8") (pintype "bidirectional"))
    )
    (net (code "40") (name "Net-(IC10A-S4)") (class "Default")
      (node (ref "IC10") (pin "15") (pinfunction "S4_15") (pintype "output"))
      (node (ref "LED24") (pin "A") (pinfunction "A_A") (pintype "passive"))
      (node (ref "V3") (pin "9") (pinfunction "A8_9") (pintype "bidirectional"))
    )
    (net (code "41") (name "Net-(IC10B-GND)") (class "Default")
      (node (ref "IC1") (pin "7") (pinfunction "GND_7") (pintype "power_in"))
      (node (ref "IC10") (pin "12") (pinfunction "GND_12") (pintype "power_in"))
      (node (ref "IC11") (pin "7") (pinfunction "GND_7") (pintype "power_in"))
      (node (ref "IC12") (pin "7") (pinfunction "GND_7") (pintype "power_in"))
      (node (ref "IC2") (pin "7") (pinfunction "GND_7") (pintype "power_in"))
      (node (ref "IC3") (pin "7") (pinfunction "GND_7") (pintype "power_in"))
      (node (ref "IC4") (pin "7") (pinfunction "GND_7") (pintype "power_in"))
      (node (ref "IC5") (pin "7") (pinfunction "GND_7") (pintype "power_in"))
      (node (ref "IC6") (pin "7") (pinfunction "GND_7") (pintype "power_in"))
      (node (ref "IC7") (pin "7") (pinfunction "GND_7") (pintype "power_in"))
      (node (ref "IC8") (pin "7") (pinfunction "GND_7") (pintype "power_in"))
      (node (ref "IC9") (pin "12") (pinfunction "GND_12") (pintype "power_in"))
      (node (ref "RN1") (pin "1") (pinfunction "1_1") (pintype "passive"))
      (node (ref "RN2") (pin "1") (pinfunction "1_1") (pintype "passive"))
      (node (ref "RN3") (pin "1") (pinfunction "1_1") (pintype "passive"))
      (node (ref "SV1") (pin "6") (pinfunction "6_6") (pintype "passive"))
      (node (ref "V1") (pin "10") (pinfunction "-UB_10") (pintype "power_in"))
      (node (ref "V2") (pin "10") (pinfunction "-UB_10") (pintype "power_in"))
      (node (ref "V3") (pin "10") (pinfunction "-UB_10") (pintype "power_in"))
      (node (ref "V4") (pin "1") (pinfunction "DIR_1") (pintype "input"))
      (node (ref "V4") (pin "10") (pinfunction "-UB_10") (pintype "power_in"))
    )
    (net (code "42") (name "Net-(IC10B-VCC)") (class "Default")
      (node (ref "IC1") (pin "10") (pinfunction "PRE_10") (pintype "input"))
      (node (ref "IC1") (pin "14") (pinfunction "VCC_14") (pintype "power_in"))
      (node (ref "IC1") (pin "4") (pinfunction "PRE_4") (pintype "input"))
      (node (ref "IC10") (pin "5") (pinfunction "VCC_5") (pintype "power_in"))
      (node (ref "IC11") (pin "14") (pinfunction "VCC_14") (pintype "power_in"))
      (node (ref "IC12") (pin "14") (pinfunction "VCC_14") (pintype "power_in"))
      (node (ref "IC2") (pin "10") (pinfunction "PRE_10") (pintype "input"))
      (node (ref "IC2") (pin "14") (pinfunction "VCC_14") (pintype "power_in"))
      (node (ref "IC2") (pin "4") (pinfunction "PRE_4") (pintype "input"))
      (node (ref "IC3") (pin "10") (pinfunction "PRE_10") (pintype "input"))
      (node (ref "IC3") (pin "14") (pinfunction "VCC_14") (pintype "power_in"))
      (node (ref "IC3") (pin "4") (pinfunction "PRE_4") (pintype "input"))
      (node (ref "IC4") (pin "10") (pinfunction "PRE_10") (pintype "input"))
      (node (ref "IC4") (pin "14") (pinfunction "VCC_14") (pintype "power_in"))
      (node (ref "IC4") (pin "4") (pinfunction "PRE_4") (pintype "input"))
      (node (ref "IC5") (pin "10") (pinfunction "PRE_10") (pintype "input"))
      (node (ref "IC5") (pin "14") (pinfunction "VCC_14") (pintype "power_in"))
      (node (ref "IC5") (pin "4") (pinfunction "PRE_4") (pintype "input"))
      (node (ref "IC6") (pin "10") (pinfunction "PRE_10") (pintype "input"))
      (node (ref "IC6") (pin "14") (pinfunction "VCC_14") (pintype "power_in"))
      (node (ref "IC6") (pin "4") (pinfunction "PRE_4") (pintype "input"))
      (node (ref "IC7") (pin "10") (pinfunction "PRE_10") (pintype "input"))
      (node (ref "IC7") (pin "14") (pinfunction "VCC_14") (pintype "power_in"))
      (node (ref "IC7") (pin "4") (pinfunction "PRE_4") (pintype "input"))
      (node (ref "IC8") (pin "10") (pinfunction "PRE_10") (pintype "input"))
      (node (ref "IC8") (pin "14") (pinfunction "VCC_14") (pintype "power_in"))
      (node (ref "IC8") (pin "4") (pinfunction "PRE_4") (pintype "input"))
      (node (ref "IC9") (pin "5") (pinfunction "VCC_5") (pintype "power_in"))
      (node (ref "SV1") (pin "5") (pinfunction "5_5") (pintype "passive"))
      (node (ref "V1") (pin "1") (pinfunction "DIR_1") (pintype "input"))
      (node (ref "V1") (pin "20") (pinfunction "+UB_20") (pintype "power_in"))
      (node (ref "V2") (pin "1") (pinfunction "DIR_1") (pintype "input"))
      (node (ref "V2") (pin "20") (pinfunction "+UB_20") (pintype "power_in"))
      (node (ref "V3") (pin "1") (pinfunction "DIR_1") (pintype "input"))
      (node (ref "V3") (pin "20") (pinfunction "+UB_20") (pintype "power_in"))
      (node (ref "V4") (pin "20") (pinfunction "+UB_20") (pintype "power_in"))
    )
    (net (code "43") (name "Net-(IC11A-I0)") (class "Default")
      (node (ref "IC11") (pin "1") (pinfunction "I0_1") (pintype "input"))
      (node (ref "IC4") (pin "9") (pinfunction "Q_9") (pintype "output"))
      (node (ref "LED1") (pin "A") (pinfunction "A_A") (pintype "passive"))
    )
    (net (code "44") (name "Net-(IC11A-I1)") (class "Default")
      (node (ref "IC11") (pin "10") (pinfunction "I1_10") (pintype "input"))
      (node (ref "IC11") (pin "13") (pinfunction "I1_13") (pintype "input"))
      (node (ref "IC11") (pin "2") (pinfunction "I1_2") (pintype "input"))
      (node (ref "IC11") (pin "5") (pinfunction "I1_5") (pintype "input"))
      (node (ref "IC12") (pin "10") (pinfunction "I1_10") (pintype "input"))
      (node (ref "IC12") (pin "13") (pinfunction "I1_13") (pintype "input"))
      (node (ref "IC12") (pin "2") (pinfunction "I1_2") (pintype "input"))
      (node (ref "IC12") (pin "5") (pinfunction "I1_5") (pintype "input"))
      (node (ref "IC9") (pin "13") (pinfunction "C0_13") (pintype "input"))
      (node (ref "SV1") (pin "7") (pinfunction "7_7") (pintype "passive"))
    )
    (net (code "45") (name "Net-(IC11A-O)") (class "Default")
      (node (ref "IC11") (pin "3") (pinfunction "O_3") (pintype "output"))
      (node (ref "IC9") (pin "11") (pinfunction "B1_11") (pintype "input"))
    )
    (net (code "46") (name "Net-(IC11B-I0)") (class "Default")
      (node (ref "IC11") (pin "4") (pinfunction "I0_4") (pintype "input"))
      (node (ref "IC3") (pin "9") (pinfunction "Q_9") (pintype "output"))
      (node (ref "LED2") (pin "A") (pinfunction "A_A") (pintype "passive"))
      (node (ref "V4") (pin "17") (pinfunction "B2_17") (pintype "bidirectional"))
    )
    (net (code "47") (name "Net-(IC11B-O)") (class "Default")
      (node (ref "IC11") (pin "6") (pinfunction "O_6") (pintype "output"))
      (node (ref "IC9") (pin "7") (pinfunction "B2_7") (pintype "input"))
    )
    (net (code "48") (name "Net-(IC11C-I0)") (class "Default")
      (node (ref "IC11") (pin "9") (pinfunction "I0_9") (pintype "input"))
      (node (ref "IC3") (pin "5") (pinfunction "Q_5") (pintype "output"))
      (node (ref "LED3") (pin "A") (pinfunction "A_A") (pintype "passive"))
      (node (ref "V4") (pin "16") (pinfunction "B3_16") (pintype "bidirectional"))
    )
    (net (code "49") (name "Net-(IC11C-O)") (class "Default")
      (node (ref "IC11") (pin "8") (pinfunction "O_8") (pintype "output"))
      (node (ref "IC9") (pin "4") (pinfunction "B3_4") (pintype "input"))
    )
    (net (code "50") (name "Net-(IC11D-I0)") (class "Default")
      (node (ref "IC11") (pin "12") (pinfunction "I0_12") (pintype "input"))
      (node (ref "IC4") (pin "5") (pinfunction "Q_5") (pintype "output"))
      (node (ref "LED4") (pin "A") (pinfunction "A_A") (pintype "passive"))
      (node (ref "V4") (pin "15") (pinfunction "B4_15") (pintype "bidirectional"))
    )
    (net (code "51") (name "Net-(IC11D-O)") (class "Default")
      (node (ref "IC11") (pin "11") (pinfunction "O_11") (pintype "output"))
      (node (ref "IC9") (pin "16") (pinfunction "B4_16") (pintype "input"))
    )
    (net (code "52") (name "Net-(IC12A-I0)") (class "Default")
      (node (ref "IC12") (pin "1") (pinfunction "I0_1") (pintype "input"))
      (node (ref "IC2") (pin "9") (pinfunction "Q_9") (pintype "output"))
      (node (ref "LED5") (pin "A") (pinfunction "A_A") (pintype "passive"))
      (node (ref "V4") (pin "14") (pinfunction "B5_14") (pintype "bidirectional"))
    )
    (net (code "53") (name "Net-(IC12B-I0)") (class "Default")
      (node (ref "IC1") (pin "9") (pinfunction "Q_9") (pintype "output"))
      (node (ref "IC12") (pin "4") (pinfunction "I0_4") (pintype "input"))
      (node (ref "LED6") (pin "A") (pinfunction "A_A") (pintype "passive"))
      (node (ref "V4") (pin "13") (pinfunction "B6_13") (pintype "bidirectional"))
    )
    (net (code "54") (name "Net-(IC12C-I0)") (class "Default")
      (node (ref "IC12") (pin "9") (pinfunction "I0_9") (pintype "input"))
      (node (ref "IC2") (pin "5") (pinfunction "Q_5") (pintype "output"))
      (node (ref "LED8") (pin "A") (pinfunction "A_A") (pintype "passive"))
      (node (ref "V4") (pin "11") (pinfunction "B8_11") (pintype "bidirectional"))
    )
    (net (code "55") (name "Net-(IC12D-I0)") (class "Default")
      (node (ref "IC1") (pin "5") (pinfunction "Q_5") (pintype "output"))
      (node (ref "IC12") (pin "12") (pinfunction "I0_12") (pintype "input"))
      (node (ref "LED7") (pin "A") (pinfunction "A_A") (pintype "passive"))
      (node (ref "V4") (pin "12") (pinfunction "B7_12") (pintype "bidirectional"))
    )
    (net (code "56") (name "Net-(LED1-C)") (class "Default")
      (node (ref "LED1") (pin "K") (pinfunction "C_K") (pintype "passive"))
      (node (ref "RN1") (pin "9") (pinfunction "9_9") (pintype "passive"))
    )
    (net (code "57") (name "Net-(LED2-C)") (class "Default")
      (node (ref "LED2") (pin "K") (pinfunction "C_K") (pintype "passive"))
      (node (ref "RN1") (pin "8") (pinfunction "8_8") (pintype "passive"))
    )
    (net (code "58") (name "Net-(LED3-C)") (class "Default")
      (node (ref "LED3") (pin "K") (pinfunction "C_K") (pintype "passive"))
      (node (ref "RN1") (pin "7") (pinfunction "7_7") (pintype "passive"))
    )
    (net (code "59") (name "Net-(LED4-C)") (class "Default")
      (node (ref "LED4") (pin "K") (pinfunction "C_K") (pintype "passive"))
      (node (ref "RN1") (pin "6") (pinfunction "6_6") (pintype "passive"))
    )
    (net (code "60") (name "Net-(LED5-C)") (class "Default")
      (node (ref "LED5") (pin "K") (pinfunction "C_K") (pintype "passive"))
      (node (ref "RN1") (pin "5") (pinfunction "5_5") (pintype "passive"))
    )
    (net (code "61") (name "Net-(LED6-C)") (class "Default")
      (node (ref "LED6") (pin "K") (pinfunction "C_K") (pintype "passive"))
      (node (ref "RN1") (pin "4") (pinfunction "4_4") (pintype "passive"))
    )
    (net (code "62") (name "Net-(LED7-C)") (class "Default")
      (node (ref "LED7") (pin "K") (pinfunction "C_K") (pintype "passive"))
      (node (ref "RN1") (pin "3") (pinfunction "3_3") (pintype "passive"))
    )
    (net (code "63") (name "Net-(LED8-C)") (class "Default")
      (node (ref "LED8") (pin "K") (pinfunction "C_K") (pintype "passive"))
      (node (ref "RN1") (pin "2") (pinfunction "2_2") (pintype "passive"))
    )
    (net (code "64") (name "Net-(LED9-C)") (class "Default")
      (node (ref "LED9") (pin "K") (pinfunction "C_K") (pintype "passive"))
      (node (ref "RN2") (pin "2") (pinfunction "2_2") (pintype "passive"))
    )
    (net (code "65") (name "Net-(LED10-C)") (class "Default")
      (node (ref "LED10") (pin "K") (pinfunction "C_K") (pintype "passive"))
      (node (ref "RN2") (pin "3") (pinfunction "3_3") (pintype "passive"))
    )
    (net (code "66") (name "Net-(LED11-C)") (class "Default")
      (node (ref "LED11") (pin "K") (pinfunction "C_K") (pintype "passive"))
      (node (ref "RN2") (pin "4") (pinfunction "4_4") (pintype "passive"))
    )
    (net (code "67") (name "Net-(LED12-C)") (class "Default")
      (node (ref "LED12") (pin "K") (pinfunction "C_K") (pintype "passive"))
      (node (ref "RN2") (pin "5") (pinfunction "5_5") (pintype "passive"))
    )
    (net (code "68") (name "Net-(LED13-C)") (class "Default")
      (node (ref "LED13") (pin "K") (pinfunction "C_K") (pintype "passive"))
      (node (ref "RN2") (pin "6") (pinfunction "6_6") (pintype "passive"))
    )
    (net (code "69") (name "Net-(LED14-C)") (class "Default")
      (node (ref "LED14") (pin "K") (pinfunction "C_K") (pintype "passive"))
      (node (ref "RN2") (pin "7") (pinfunction "7_7") (pintype "passive"))
    )
    (net (code "70") (name "Net-(LED15-C)") (class "Default")
      (node (ref "LED15") (pin "K") (pinfunction "C_K") (pintype "passive"))
      (node (ref "RN2") (pin "8") (pinfunction "8_8") (pintype "passive"))
    )
    (net (code "71") (name "Net-(LED16-C)") (class "Default")
      (node (ref "LED16") (pin "K") (pinfunction "C_K") (pintype "passive"))
      (node (ref "RN2") (pin "9") (pinfunction "9_9") (pintype "passive"))
    )
    (net (code "72") (name "Net-(LED17-C)") (class "Default")
      (node (ref "LED17") (pin "K") (pinfunction "C_K") (pintype "passive"))
      (node (ref "RN3") (pin "2") (pinfunction "2_2") (pintype "passive"))
    )
    (net (code "73") (name "Net-(LED18-C)") (class "Default")
      (node (ref "LED18") (pin "K") (pinfunction "C_K") (pintype "passive"))
      (node (ref "RN3") (pin "3") (pinfunction "3_3") (pintype "passive"))
    )
    (net (code "74") (name "Net-(LED19-C)") (class "Default")
      (node (ref "LED19") (pin "K") (pinfunction "C_K") (pintype "passive"))
      (node (ref "RN3") (pin "4") (pinfunction "4_4") (pintype "passive"))
    )
    (net (code "75") (name "Net-(LED20-C)") (class "Default")
      (node (ref "LED20") (pin "K") (pinfunction "C_K") (pintype "passive"))
      (node (ref "RN3") (pin "5") (pinfunction "5_5") (pintype "passive"))
    )
    (net (code "76") (name "Net-(LED21-C)") (class "Default")
      (node (ref "LED21") (pin "K") (pinfunction "C_K") (pintype "passive"))
      (node (ref "RN3") (pin "6") (pinfunction "6_6") (pintype "passive"))
    )
    (net (code "77") (name "Net-(LED22-C)") (class "Default")
      (node (ref "LED22") (pin "K") (pinfunction "C_K") (pintype "passive"))
      (node (ref "RN3") (pin "7") (pinfunction "7_7") (pintype "passive"))
    )
    (net (code "78") (name "Net-(LED23-C)") (class "Default")
      (node (ref "LED23") (pin "K") (pinfunction "C_K") (pintype "passive"))
      (node (ref "RN3") (pin "8") (pinfunction "8_8") (pintype "passive"))
    )
    (net (code "79") (name "Net-(LED24-C)") (class "Default")
      (node (ref "LED24") (pin "K") (pinfunction "C_K") (pintype "passive"))
      (node (ref "RN3") (pin "9") (pinfunction "9_9") (pintype "passive"))
    )
    (net (code "80") (name "Net-(V1C-A1)") (class "Default")
      (node (ref "SV2") (pin "8") (pinfunction "8_8") (pintype "passive"))
      (node (ref "V1") (pin "2") (pinfunction "A1_2") (pintype "bidirectional"))
      (node (ref "V2") (pin "2") (pinfunction "A1_2") (pintype "bidirectional"))
      (node (ref "V3") (pin "18") (pinfunction "B1_18") (pintype "bidirectional"))
      (node (ref "V4") (pin "2") (pinfunction "A1_2") (pintype "bidirectional"))
    )
    (net (code "81") (name "Net-(V1C-A2)") (class "Default")
      (node (ref "SV2") (pin "7") (pinfunction "7_7") (pintype "passive"))
      (node (ref "V1") (pin "3") (pinfunction "A2_3") (pintype "bidirectional"))
      (node (ref "V2") (pin "3") (pinfunction "A2_3") (pintype "bidirectional"))
      (node (ref "V3") (pin "17") (pinfunction "B2_17") (pintype "bidirectional"))
      (node (ref "V4") (pin "3") (pinfunction "A2_3") (pintype "bidirectional"))
    )
    (net (code "82") (name "Net-(V1C-A3)") (class "Default")
      (node (ref "SV2") (pin "6") (pinfunction "6_6") (pintype "passive"))
      (node (ref "V1") (pin "4") (pinfunction "A3_4") (pintype "bidirectional"))
      (node (ref "V2") (pin "4") (pinfunction "A3_4") (pintype "bidirectional"))
      (node (ref "V3") (pin "16") (pinfunction "B3_16") (pintype "bidirectional"))
      (node (ref "V4") (pin "4") (pinfunction "A3_4") (pintype "bidirectional"))
    )
    (net (code "83") (name "Net-(V1C-A4)") (class "Default")
      (node (ref "SV2") (pin "5") (pinfunction "5_5") (pintype "passive"))
      (node (ref "V1") (pin "5") (pinfunction "A4_5") (pintype "bidirectional"))
      (node (ref "V2") (pin "5") (pinfunction "A4_5") (pintype "bidirectional"))
      (node (ref "V3") (pin "15") (pinfunction "B4_15") (pintype "bidirectional"))
      (node (ref "V4") (pin "5") (pinfunction "A4_5") (pintype "bidirectional"))
    )
    (net (code "84") (name "Net-(V1C-A5)") (class "Default")
      (node (ref "SV2") (pin "4") (pinfunction "4_4") (pintype "passive"))
      (node (ref "V1") (pin "6") (pinfunction "A5_6") (pintype "bidirectional"))
      (node (ref "V2") (pin "6") (pinfunction "A5_6") (pintype "bidirectional"))
      (node (ref "V3") (pin "14") (pinfunction "B5_14") (pintype "bidirectional"))
      (node (ref "V4") (pin "6") (pinfunction "A5_6") (pintype "bidirectional"))
    )
    (net (code "85") (name "Net-(V1C-A6)") (class "Default")
      (node (ref "SV2") (pin "3") (pinfunction "3_3") (pintype "passive"))
      (node (ref "V1") (pin "7") (pinfunction "A6_7") (pintype "bidirectional"))
      (node (ref "V2") (pin "7") (pinfunction "A6_7") (pintype "bidirectional"))
      (node (ref "V3") (pin "13") (pinfunction "B6_13") (pintype "bidirectional"))
      (node (ref "V4") (pin "7") (pinfunction "A6_7") (pintype "bidirectional"))
    )
    (net (code "86") (name "Net-(V1C-A7)") (class "Default")
      (node (ref "SV2") (pin "2") (pinfunction "2_2") (pintype "passive"))
      (node (ref "V1") (pin "8") (pinfunction "A7_8") (pintype "bidirectional"))
      (node (ref "V2") (pin "8") (pinfunction "A7_8") (pintype "bidirectional"))
      (node (ref "V3") (pin "12") (pinfunction "B7_12") (pintype "bidirectional"))
      (node (ref "V4") (pin "8") (pinfunction "A7_8") (pintype "bidirectional"))
    )
    (net (code "87") (name "Net-(V1C-A8)") (class "Default")
      (node (ref "SV2") (pin "1") (pinfunction "1_1") (pintype "passive"))
      (node (ref "V1") (pin "9") (pinfunction "A8_9") (pintype "bidirectional"))
      (node (ref "V2") (pin "9") (pinfunction "A8_9") (pintype "bidirectional"))
      (node (ref "V3") (pin "11") (pinfunction "B8_11") (pintype "bidirectional"))
      (node (ref "V4") (pin "9") (pinfunction "A8_9") (pintype "bidirectional"))
    )
    (net (code "88") (name "Net-(V1C-B1)") (class "Default")
      (node (ref "R16") (pin "1") (pinfunction "1_1") (pintype "passive"))
      (node (ref "V1") (pin "18") (pinfunction "B1_18") (pintype "bidirectional"))
    )
    (net (code "89") (name "Net-(V1C-B2)") (class "Default")
      (node (ref "R15") (pin "1") (pinfunction "1_1") (pintype "passive"))
      (node (ref "V1") (pin "17") (pinfunction "B2_17") (pintype "bidirectional"))
    )
    (net (code "90") (name "Net-(V1C-B3)") (class "Default")
      (node (ref "R14") (pin "1") (pinfunction "1_1") (pintype "passive"))
      (node (ref "V1") (pin "16") (pinfunction "B3_16") (pintype "bidirectional"))
    )
    (net (code "91") (name "Net-(V1C-B4)") (class "Default")
      (node (ref "R13") (pin "1") (pinfunction "1_1") (pintype "passive"))
      (node (ref "V1") (pin "15") (pinfunction "B4_15") (pintype "bidirectional"))
    )
    (net (code "92") (name "Net-(V1C-B5)") (class "Default")
      (node (ref "R12") (pin "1") (pinfunction "1_1") (pintype "passive"))
      (node (ref "V1") (pin "14") (pinfunction "B5_14") (pintype "bidirectional"))
    )
    (net (code "93") (name "Net-(V1C-B6)") (class "Default")
      (node (ref "R11") (pin "1") (pinfunction "1_1") (pintype "passive"))
      (node (ref "V1") (pin "13") (pinfunction "B6_13") (pintype "bidirectional"))
    )
    (net (code "94") (name "Net-(V1C-B7)") (class "Default")
      (node (ref "R10") (pin "1") (pinfunction "1_1") (pintype "passive"))
      (node (ref "V1") (pin "12") (pinfunction "B7_12") (pintype "bidirectional"))
    )
    (net (code "95") (name "Net-(V1C-B8)") (class "Default")
      (node (ref "R9") (pin "1") (pinfunction "1_1") (pintype "passive"))
      (node (ref "V1") (pin "11") (pinfunction "B8_11") (pintype "bidirectional"))
    )
    (net (code "96") (name "Net-(V1C-~{G})") (class "Default")
      (node (ref "SV1") (pin "4") (pinfunction "4_4") (pintype "passive"))
      (node (ref "V1") (pin "19") (pinfunction "~{G}_19") (pintype "input"))
    )
    (net (code "97") (name "Net-(V2C-B1)") (class "Default")
      (node (ref "R8") (pin "1") (pinfunction "1_1") (pintype "passive"))
      (node (ref "V2") (pin "18") (pinfunction "B1_18") (pintype "bidirectional"))
    )
    (net (code "98") (name "Net-(V2C-B2)") (class "Default")
      (node (ref "R4") (pin "1") (pinfunction "1_1") (pintype "passive"))
      (node (ref "V2") (pin "17") (pinfunction "B2_17") (pintype "bidirectional"))
    )
    (net (code "99") (name "Net-(V2C-B3)") (class "Default")
      (node (ref "R5") (pin "1") (pinfunction "1_1") (pintype "passive"))
      (node (ref "V2") (pin "16") (pinfunction "B3_16") (pintype "bidirectional"))
    )
    (net (code "100") (name "Net-(V2C-B4)") (class "Default")
      (node (ref "R6") (pin "1") (pinfunction "1_1") (pintype "passive"))
      (node (ref "V2") (pin "15") (pinfunction "B4_15") (pintype "bidirectional"))
    )
    (net (code "101") (name "Net-(V2C-B5)") (class "Default")
      (node (ref "R7") (pin "1") (pinfunction "1_1") (pintype "passive"))
      (node (ref "V2") (pin "14") (pinfunction "B5_14") (pintype "bidirectional"))
    )
    (net (code "102") (name "Net-(V2C-B6)") (class "Default")
      (node (ref "R3") (pin "1") (pinfunction "1_1") (pintype "passive"))
      (node (ref "V2") (pin "13") (pinfunction "B6_13") (pintype "bidirectional"))
    )
    (net (code "103") (name "Net-(V2C-B7)") (class "Default")
      (node (ref "R2") (pin "1") (pinfunction "1_1") (pintype "passive"))
      (node (ref "V2") (pin "12") (pinfunction "B7_12") (pintype "bidirectional"))
    )
    (net (code "104") (name "Net-(V2C-B8)") (class "Default")
      (node (ref "R1") (pin "1") (pinfunction "1_1") (pintype "passive"))
      (node (ref "V2") (pin "11") (pinfunction "B8_11") (pintype "bidirectional"))
    )
    (net (code "105") (name "Net-(V2C-~{G})") (class "Default")
      (node (ref "SV1") (pin "3") (pinfunction "3_3") (pintype "passive"))
      (node (ref "V2") (pin "19") (pinfunction "~{G}_19") (pintype "input"))
    )
    (net (code "106") (name "Net-(V3C-~{G})") (class "Default")
      (node (ref "SV1") (pin "1") (pinfunction "1_1") (pintype "passive"))
      (node (ref "V3") (pin "19") (pinfunction "~{G}_19") (pintype "input"))
    )
    (net (code "107") (name "Net-(V4C-~{G})") (class "Default")
      (node (ref "SV1") (pin "2") (pinfunction "2_2") (pintype "passive"))
      (node (ref "V4") (pin "19") (pinfunction "~{G}_19") (pintype "input"))
    )
    (net (code "108") (name "unconnected-(IC1A-~{Q}-Pad6)") (class "Default")
      (node (ref "IC1") (pin "6") (pinfunction "~{Q}_6") (pintype "output"))
    )
    (net (code "109") (name "unconnected-(IC1B-~{Q}-Pad8)") (class "Default")
      (node (ref "IC1") (pin "8") (pinfunction "~{Q}_8") (pintype "output"))
    )
    (net (code "110") (name "unconnected-(IC2A-~{Q}-Pad6)") (class "Default")
      (node (ref "IC2") (pin "6") (pinfunction "~{Q}_6") (pintype "output"))
    )
    (net (code "111") (name "unconnected-(IC2B-~{Q}-Pad8)") (class "Default")
      (node (ref "IC2") (pin "8") (pinfunction "~{Q}_8") (pintype "output"))
    )
    (net (code "112") (name "unconnected-(IC3A-~{Q}-Pad6)") (class "Default")
      (node (ref "IC3") (pin "6") (pinfunction "~{Q}_6") (pintype "output"))
    )
    (net (code "113") (name "unconnected-(IC3B-~{Q}-Pad8)") (class "Default")
      (node (ref "IC3") (pin "8") (pinfunction "~{Q}_8") (pintype "output"))
    )
    (net (code "114") (name "unconnected-(IC4A-~{Q}-Pad6)") (class "Default")
      (node (ref "IC4") (pin "6") (pinfunction "~{Q}_6") (pintype "output"))
    )
    (net (code "115") (name "unconnected-(IC4B-~{Q}-Pad8)") (class "Default")
      (node (ref "IC4") (pin "8") (pinfunction "~{Q}_8") (pintype "output"))
    )
    (net (code "116") (name "unconnected-(IC5A-~{Q}-Pad6)") (class "Default")
      (node (ref "IC5") (pin "6") (pinfunction "~{Q}_6") (pintype "output"))
    )
    (net (code "117") (name "unconnected-(IC5B-~{Q}-Pad8)") (class "Default")
      (node (ref "IC5") (pin "8") (pinfunction "~{Q}_8") (pintype "output"))
    )
    (net (code "118") (name "unconnected-(IC6A-~{Q}-Pad6)") (class "Default")
      (node (ref "IC6") (pin "6") (pinfunction "~{Q}_6") (pintype "output"))
    )
    (net (code "119") (name "unconnected-(IC6B-~{Q}-Pad8)") (class "Default")
      (node (ref "IC6") (pin "8") (pinfunction "~{Q}_8") (pintype "output"))
    )
    (net (code "120") (name "unconnected-(IC7A-~{Q}-Pad6)") (class "Default")
      (node (ref "IC7") (pin "6") (pinfunction "~{Q}_6") (pintype "output"))
    )
    (net (code "121") (name "unconnected-(IC7B-~{Q}-Pad8)") (class "Default")
      (node (ref "IC7") (pin "8") (pinfunction "~{Q}_8") (pintype "output"))
    )
    (net (code "122") (name "unconnected-(IC8A-~{Q}-Pad6)") (class "Default")
      (node (ref "IC8") (pin "6") (pinfunction "~{Q}_6") (pintype "output"))
    )
    (net (code "123") (name "unconnected-(IC8B-~{Q}-Pad8)") (class "Default")
      (node (ref "IC8") (pin "8") (pinfunction "~{Q}_8") (pintype "output"))
    )
    (net (code "124") (name "unconnected-(IC10A-C4-Pad14)") (class "Default")
      (node (ref "IC10") (pin "14") (pinfunction "C4_14") (pintype "output"))
    )
    (net (code "125") (name "unconnected-(SV3-Pad1)") (class "Default")
      (node (ref "SV3") (pin "1") (pinfunction "1_1") (pintype "passive"))
    )
    (net (code "126") (name "unconnected-(SV3-Pad2)") (class "Default")
      (node (ref "SV3") (pin "2") (pinfunction "2_2") (pintype "passive"))
    )
    (net (code "127") (name "unconnected-(SV3-Pad3)") (class "Default")
      (node (ref "SV3") (pin "3") (pinfunction "3_3") (pintype "passive"))
    )
    (net (code "128") (name "unconnected-(SV3-Pad4)") (class "Default")
      (node (ref "SV3") (pin "4") (pinfunction "4_4") (pintype "passive"))
    )
    (net (code "129") (name "unconnected-(SV3-Pad5)") (class "Default")
      (node (ref "SV3") (pin "5") (pinfunction "5_5") (pintype "passive"))
    )
    (net (code "130") (name "unconnected-(SV3-Pad6)") (class "Default")
      (node (ref "SV3") (pin "6") (pinfunction "6_6") (pintype "passive"))
    )
    (net (code "131") (name "unconnected-(SV4-Pad1)") (class "Default")
      (node (ref "SV4") (pin "1") (pinfunction "1_1") (pintype "passive"))
    )
    (net (code "132") (name "unconnected-(SV4-Pad2)") (class "Default")
      (node (ref "SV4") (pin "2") (pinfunction "2_2") (pintype "passive"))
    )
    (net (code "133") (name "unconnected-(SV4-Pad3)") (class "Default")
      (node (ref "SV4") (pin "3") (pinfunction "3_3") (pintype "passive"))
    )
    (net (code "134") (name "unconnected-(SV4-Pad4)") (class "Default")
      (node (ref "SV4") (pin "4") (pinfunction "4_4") (pintype "passive"))
    )
    (net (code "135") (name "unconnected-(SV5-Pad1)") (class "Default")
      (node (ref "SV5") (pin "1") (pinfunction "1_1") (pintype "passive"))
    )
    (net (code "136") (name "unconnected-(SV5-Pad2)") (class "Default")
      (node (ref "SV5") (pin "2") (pinfunction "2_2") (pintype "passive"))
    )
    (net (code "137") (name "unconnected-(SV5-Pad3)") (class "Default")
      (node (ref "SV5") (pin "3") (pinfunction "3_3") (pintype "passive"))
    )
    (net (code "138") (name "unconnected-(SV5-Pad4)") (class "Default")
      (node (ref "SV5") (pin "4") (pinfunction "4_4") (pintype "passive"))
    )
    (net (code "139") (name "unconnected-(SV6-Pad1)") (class "Default")
      (node (ref "SV6") (pin "1") (pinfunction "1_1") (pintype "passive"))
    )
    (net (code "140") (name "unconnected-(SV6-Pad2)") (class "Default")
      (node (ref "SV6") (pin "2") (pinfunction "2_2") (pintype "passive"))
    )
    (net (code "141") (name "unconnected-(SV6-Pad3)") (class "Default")
      (node (ref "SV6") (pin "3") (pinfunction "3_3") (pintype "passive"))
    )
    (net (code "142") (name "unconnected-(SV6-Pad4)") (class "Default")
      (node (ref "SV6") (pin "4") (pinfunction "4_4") (pintype "passive"))
    )
    (net (code "143") (name "unconnected-(SV6-Pad5)") (class "Default")
      (node (ref "SV6") (pin "5") (pinfunction "5_5") (pintype "passive"))
    )
    (net (code "144") (name "unconnected-(SV6-Pad6)") (class "Default")
      (node (ref "SV6") (pin "6") (pinfunction "6_6") (pintype "passive"))
    )
    (net (code "145") (name "unconnected-(SV6-Pad7)") (class "Default")
      (node (ref "SV6") (pin "7") (pinfunction "7_7") (pintype "passive"))
    )
    (net (code "146") (name "unconnected-(SV6-Pad8)") (class "Default")
      (node (ref "SV6") (pin "8") (pinfunction "8_8") (pintype "passive"))
    )
    (net (code "147") (name "unconnected-(SV7-Pad1)") (class "Default")
      (node (ref "SV7") (pin "1") (pinfunction "1_1") (pintype "passive"))
    )
    (net (code "148") (name "unconnected-(SV7-Pad2)") (class "Default")
      (node (ref "SV7") (pin "2") (pinfunction "2_2") (pintype "passive"))
    )
    (net (code "149") (name "unconnected-(SV7-Pad3)") (class "Default")
      (node (ref "SV7") (pin "3") (pinfunction "3_3") (pintype "passive"))
    )
    (net (code "150") (name "unconnected-(SV7-Pad4)") (class "Default")
      (node (ref "SV7") (pin "4") (pinfunction "4_4") (pintype "passive"))
    )
    (net (code "151") (name "unconnected-(SV7-Pad5)") (class "Default")
      (node (ref "SV7") (pin "5") (pinfunction "5_5") (pintype "passive"))
    )
    (net (code "152") (name "unconnected-(SV7-Pad6)") (class "Default")
      (node (ref "SV7") (pin "6") (pinfunction "6_6") (pintype "passive"))
    )
    (net (code "153") (name "unconnected-(SV7-Pad7)") (class "Default")
      (node (ref "SV7") (pin "7") (pinfunction "7_7") (pintype "passive"))
    )
    (net (code "154") (name "unconnected-(SV7-Pad8)") (class "Default")
      (node (ref "SV7") (pin "8") (pinfunction "8_8") (pintype "passive"))
    )
    (net (code "155") (name "unconnected-(SV8-Pad1)") (class "Default")
      (node (ref "SV8") (pin "1") (pinfunction "1_1") (pintype "passive"))
    )
    (net (code "156") (name "unconnected-(SV8-Pad2)") (class "Default")
      (node (ref "SV8") (pin "2") (pinfunction "2_2") (pintype "passive"))
    )
    (net (code "157") (name "unconnected-(SV8-Pad3)") (class "Default")
      (node (ref "SV8") (pin "3") (pinfunction "3_3") (pintype "passive"))
    )
    (net (code "158") (name "unconnected-(SV8-Pad4)") (class "Default")
      (node (ref "SV8") (pin "4") (pinfunction "4_4") (pintype "passive"))
    )
    (net (code "159") (name "unconnected-(SV8-Pad5)") (class "Default")
      (node (ref "SV8") (pin "5") (pinfunction "5_5") (pintype "passive"))
    )
    (net (code "160") (name "unconnected-(SV8-Pad6)") (class "Default")
      (node (ref "SV8") (pin "6") (pinfunction "6_6") (pintype "passive"))
    )
    (net (code "161") (name "unconnected-(SV8-Pad7)") (class "Default")
      (node (ref "SV8") (pin "7") (pinfunction "7_7") (pintype "passive"))
    )
    (net (code "162") (name "unconnected-(SV8-Pad8)") (class "Default")
      (node (ref "SV8") (pin "8") (pinfunction "8_8") (pintype "passive"))
    )
    (net (code "163") (name "unconnected-(SV8-Pad9)") (class "Default")
      (node (ref "SV8") (pin "9") (pinfunction "9_9") (pintype "passive"))
    )
    (net (code "164") (name "unconnected-(SV8-Pad10)") (class "Default")
      (node (ref "SV8") (pin "10") (pinfunction "10_10") (pintype "passive"))
    )
    (net (code "165") (name "unconnected-(V4C-B1-Pad18)") (class "Default")
      (node (ref "V4") (pin "18") (pinfunction "B1_18") (pintype "bidirectional"))
    )
  )
)
